# PhotonOnAStick-Wide.net
KiCad netlist of a schematic drawn in EAGLE
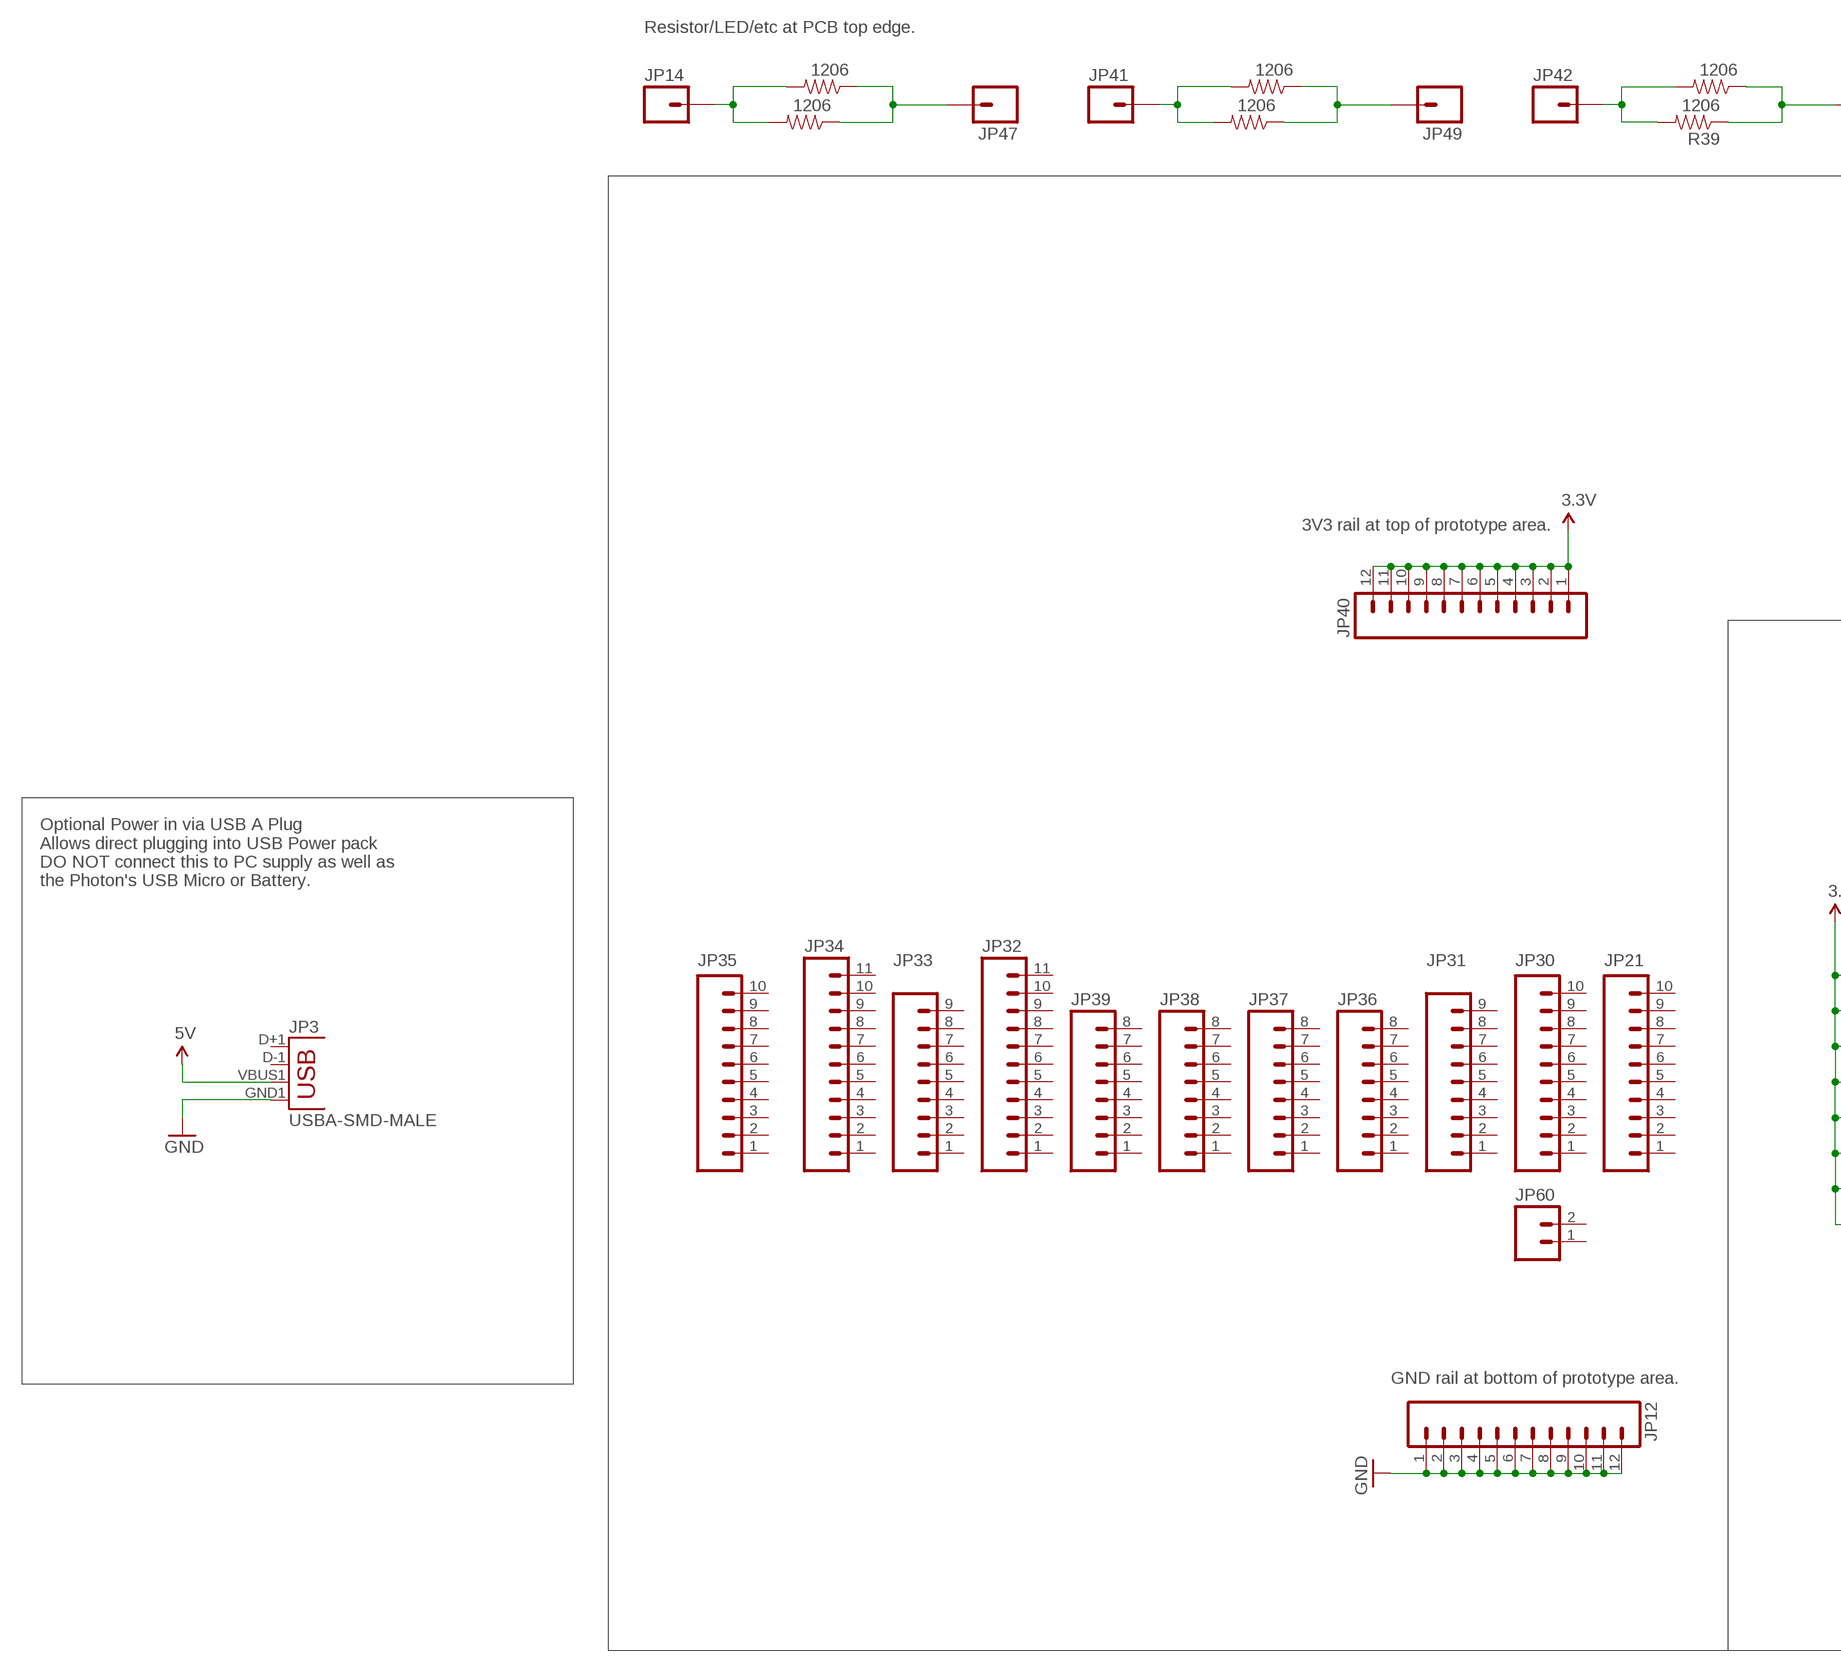
[diagram p0: schematic, sheet 1, part 1 of 2]
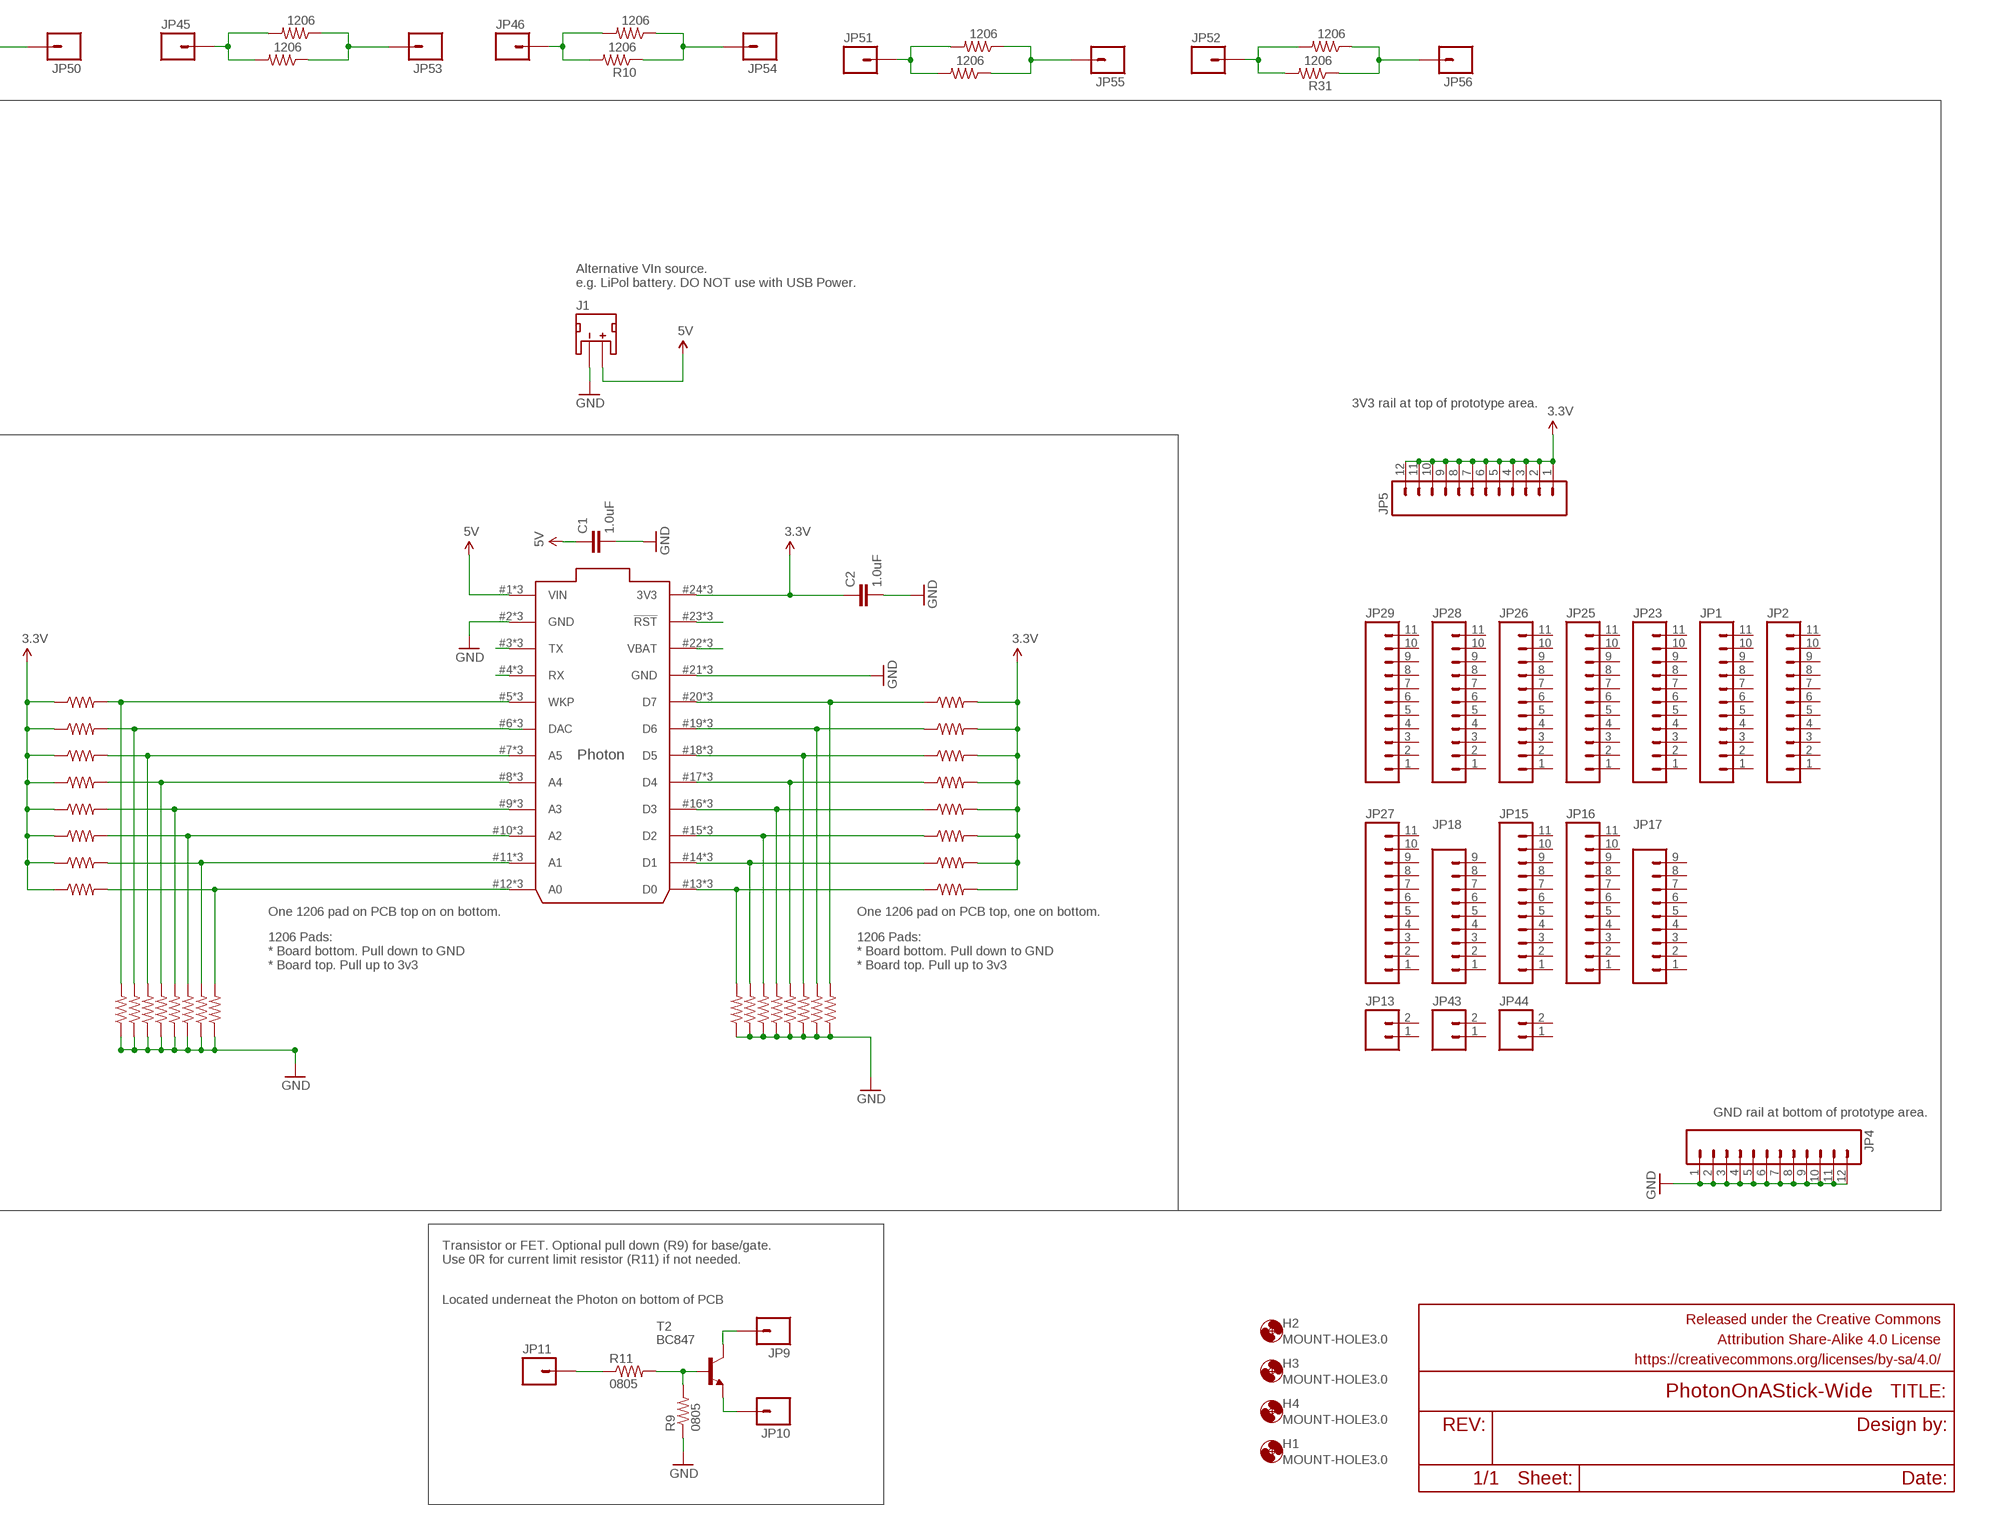
[diagram p1: schematic, sheet 1, part 2 of 2]

(export (version "E")
  (design (tool "Eeschema 10.0.6"))
  (components
    (comp (ref "C1")
      (value "1.0uF")
      (footprint "eagle-import:0805-CAP")
      (libsource (lib "eagle-import") (part "1.0UF-25V-+80/-20(0805){dblquote}"))
    )
    (comp (ref "C2")
      (value "1.0uF")
      (footprint "eagle-import:0805-CAP")
      (libsource (lib "eagle-import") (part "1.0UF-25V-+80/-20(0805){dblquote}"))
    )
    (comp (ref "FRAME1")
      (value "FRAME-LEDGER")
      (footprint "eagle-import:CREATIVE_COMMONS")
      (libsource (lib "eagle-import") (part "FRAME-LEDGER"))
    )
    (comp (ref "H1")
      (value "MOUNT-HOLE3.0")
      (footprint "eagle-import:3,0")
      (libsource (lib "eagle-import") (part "MOUNT-HOLE3.0"))
    )
    (comp (ref "H2")
      (value "MOUNT-HOLE3.0")
      (footprint "eagle-import:3,0")
      (libsource (lib "eagle-import") (part "MOUNT-HOLE3.0"))
    )
    (comp (ref "H3")
      (value "MOUNT-HOLE3.0")
      (footprint "eagle-import:3,0")
      (libsource (lib "eagle-import") (part "MOUNT-HOLE3.0"))
    )
    (comp (ref "H4")
      (value "MOUNT-HOLE3.0")
      (footprint "eagle-import:3,0")
      (libsource (lib "eagle-import") (part "MOUNT-HOLE3.0"))
    )
    (comp (ref "IC1")
      (value "PHOTON_WITH_STACKABLE_HEADERS")
      (footprint "eagle-import:PHOTON_STACKABLE")
      (libsource (lib "eagle-import") (part "PHOTON_WITH_STACKABLE_HEADERS"))
    )
    (comp (ref "J1")
      (value "JST_2MM_MALE")
      (footprint "eagle-import:JST-2-SMD")
      (libsource (lib "eagle-import") (part "JST_2MM_MALE"))
    )
    (comp (ref "JP1")
      (value "M111X11_NO_SILK")
      (footprint "eagle-import:1X11_NO_SILK")
      (libsource (lib "eagle-import") (part "M111X11_NO_SILK"))
    )
    (comp (ref "JP2")
      (value "M111X11_NO_SILK")
      (footprint "eagle-import:1X11_NO_SILK")
      (libsource (lib "eagle-import") (part "M111X11_NO_SILK"))
    )
    (comp (ref "JP3")
      (value "USBA-SMD-MALE")
      (footprint "eagle-import:USB-A-SMT-MALE")
      (libsource (lib "eagle-import") (part "USBA-SMD-MALE"))
    )
    (comp (ref "JP4")
      (value "M12PTH")
      (footprint "eagle-import:1X12")
      (libsource (lib "eagle-import") (part "M12PTH"))
    )
    (comp (ref "JP5")
      (value "M12PTH")
      (footprint "eagle-import:1X12")
      (libsource (lib "eagle-import") (part "M12PTH"))
    )
    (comp (ref "JP9")
      (value "M01PTH")
      (footprint "eagle-import:1X01")
      (libsource (lib "eagle-import") (part "M01PTH"))
    )
    (comp (ref "JP10")
      (value "M01PTH")
      (footprint "eagle-import:1X01")
      (libsource (lib "eagle-import") (part "M01PTH"))
    )
    (comp (ref "JP11")
      (value "M01PTH")
      (footprint "eagle-import:1X01")
      (libsource (lib "eagle-import") (part "M01PTH"))
    )
    (comp (ref "JP12")
      (value "M12PTH")
      (footprint "eagle-import:1X12")
      (libsource (lib "eagle-import") (part "M12PTH"))
    )
    (comp (ref "JP13")
      (value "M021X02_NO_SILK")
      (footprint "eagle-import:1X02_NO_SILK")
      (libsource (lib "eagle-import") (part "M021X02_NO_SILK"))
    )
    (comp (ref "JP14")
      (value "M01PTH")
      (footprint "eagle-import:1X01")
      (libsource (lib "eagle-import") (part "M01PTH"))
    )
    (comp (ref "JP15")
      (value "M111X11_NO_SILK")
      (footprint "eagle-import:1X11_NO_SILK")
      (libsource (lib "eagle-import") (part "M111X11_NO_SILK"))
    )
    (comp (ref "JP16")
      (value "M111X11_NO_SILK")
      (footprint "eagle-import:1X11_NO_SILK")
      (libsource (lib "eagle-import") (part "M111X11_NO_SILK"))
    )
    (comp (ref "JP17")
      (value "M09NO_SILK")
      (footprint "eagle-import:1X09_NO_SILK")
      (libsource (lib "eagle-import") (part "M09NO_SILK"))
    )
    (comp (ref "JP18")
      (value "M09NO_SILK")
      (footprint "eagle-import:1X09_NO_SILK")
      (libsource (lib "eagle-import") (part "M09NO_SILK"))
    )
    (comp (ref "JP21")
      (value "M10NO_SILK_PTH_FEMALE")
      (footprint "eagle-import:1X10_NO_SILK")
      (libsource (lib "eagle-import") (part "M10NO_SILK_PTH_FEMALE"))
    )
    (comp (ref "JP23")
      (value "M111X11_NO_SILK")
      (footprint "eagle-import:1X11_NO_SILK")
      (libsource (lib "eagle-import") (part "M111X11_NO_SILK"))
    )
    (comp (ref "JP25")
      (value "M111X11_NO_SILK")
      (footprint "eagle-import:1X11_NO_SILK")
      (libsource (lib "eagle-import") (part "M111X11_NO_SILK"))
    )
    (comp (ref "JP26")
      (value "M111X11_NO_SILK")
      (footprint "eagle-import:1X11_NO_SILK")
      (libsource (lib "eagle-import") (part "M111X11_NO_SILK"))
    )
    (comp (ref "JP27")
      (value "M111X11_NO_SILK")
      (footprint "eagle-import:1X11_NO_SILK")
      (libsource (lib "eagle-import") (part "M111X11_NO_SILK"))
    )
    (comp (ref "JP28")
      (value "M111X11_NO_SILK")
      (footprint "eagle-import:1X11_NO_SILK")
      (libsource (lib "eagle-import") (part "M111X11_NO_SILK"))
    )
    (comp (ref "JP29")
      (value "M111X11_NO_SILK")
      (footprint "eagle-import:1X11_NO_SILK")
      (libsource (lib "eagle-import") (part "M111X11_NO_SILK"))
    )
    (comp (ref "JP30")
      (value "M10NO_SILK_PTH_FEMALE")
      (footprint "eagle-import:1X10_NO_SILK")
      (libsource (lib "eagle-import") (part "M10NO_SILK_PTH_FEMALE"))
    )
    (comp (ref "JP31")
      (value "M09NO_SILK")
      (footprint "eagle-import:1X09_NO_SILK")
      (libsource (lib "eagle-import") (part "M09NO_SILK"))
    )
    (comp (ref "JP32")
      (value "M111X11_NO_SILK")
      (footprint "eagle-import:1X11_NO_SILK")
      (libsource (lib "eagle-import") (part "M111X11_NO_SILK"))
    )
    (comp (ref "JP33")
      (value "M09NO_SILK")
      (footprint "eagle-import:1X09_NO_SILK")
      (libsource (lib "eagle-import") (part "M09NO_SILK"))
    )
    (comp (ref "JP34")
      (value "M111X11_NO_SILK")
      (footprint "eagle-import:1X11_NO_SILK")
      (libsource (lib "eagle-import") (part "M111X11_NO_SILK"))
    )
    (comp (ref "JP35")
      (value "M10NO_SILK_PTH_FEMALE")
      (footprint "eagle-import:1X10_NO_SILK")
      (libsource (lib "eagle-import") (part "M10NO_SILK_PTH_FEMALE"))
    )
    (comp (ref "JP36")
      (value "M08NO_SILK_FEMALE_PTH")
      (footprint "eagle-import:1X08_NO_SILK")
      (libsource (lib "eagle-import") (part "M08NO_SILK_FEMALE_PTH"))
    )
    (comp (ref "JP37")
      (value "M08NO_SILK_FEMALE_PTH")
      (footprint "eagle-import:1X08_NO_SILK")
      (libsource (lib "eagle-import") (part "M08NO_SILK_FEMALE_PTH"))
    )
    (comp (ref "JP38")
      (value "M08NO_SILK_FEMALE_PTH")
      (footprint "eagle-import:1X08_NO_SILK")
      (libsource (lib "eagle-import") (part "M08NO_SILK_FEMALE_PTH"))
    )
    (comp (ref "JP39")
      (value "M08NO_SILK_FEMALE_PTH")
      (footprint "eagle-import:1X08_NO_SILK")
      (libsource (lib "eagle-import") (part "M08NO_SILK_FEMALE_PTH"))
    )
    (comp (ref "JP40")
      (value "M12PTH")
      (footprint "eagle-import:1X12")
      (libsource (lib "eagle-import") (part "M12PTH"))
    )
    (comp (ref "JP41")
      (value "M01PTH")
      (footprint "eagle-import:1X01")
      (libsource (lib "eagle-import") (part "M01PTH"))
    )
    (comp (ref "JP42")
      (value "M01PTH")
      (footprint "eagle-import:1X01")
      (libsource (lib "eagle-import") (part "M01PTH"))
    )
    (comp (ref "JP43")
      (value "M021X02_NO_SILK")
      (footprint "eagle-import:1X02_NO_SILK")
      (libsource (lib "eagle-import") (part "M021X02_NO_SILK"))
    )
    (comp (ref "JP44")
      (value "M021X02_NO_SILK")
      (footprint "eagle-import:1X02_NO_SILK")
      (libsource (lib "eagle-import") (part "M021X02_NO_SILK"))
    )
    (comp (ref "JP45")
      (value "M01PTH")
      (footprint "eagle-import:1X01")
      (libsource (lib "eagle-import") (part "M01PTH"))
    )
    (comp (ref "JP46")
      (value "M01PTH")
      (footprint "eagle-import:1X01")
      (libsource (lib "eagle-import") (part "M01PTH"))
    )
    (comp (ref "JP47")
      (value "M01PTH")
      (footprint "eagle-import:1X01")
      (libsource (lib "eagle-import") (part "M01PTH"))
    )
    (comp (ref "JP49")
      (value "M01PTH")
      (footprint "eagle-import:1X01")
      (libsource (lib "eagle-import") (part "M01PTH"))
    )
    (comp (ref "JP50")
      (value "M01PTH")
      (footprint "eagle-import:1X01")
      (libsource (lib "eagle-import") (part "M01PTH"))
    )
    (comp (ref "JP51")
      (value "M01PTH")
      (footprint "eagle-import:1X01")
      (libsource (lib "eagle-import") (part "M01PTH"))
    )
    (comp (ref "JP52")
      (value "M01PTH")
      (footprint "eagle-import:1X01")
      (libsource (lib "eagle-import") (part "M01PTH"))
    )
    (comp (ref "JP53")
      (value "M01PTH")
      (footprint "eagle-import:1X01")
      (libsource (lib "eagle-import") (part "M01PTH"))
    )
    (comp (ref "JP54")
      (value "M01PTH")
      (footprint "eagle-import:1X01")
      (libsource (lib "eagle-import") (part "M01PTH"))
    )
    (comp (ref "JP55")
      (value "M01PTH")
      (footprint "eagle-import:1X01")
      (libsource (lib "eagle-import") (part "M01PTH"))
    )
    (comp (ref "JP56")
      (value "M01PTH")
      (footprint "eagle-import:1X01")
      (libsource (lib "eagle-import") (part "M01PTH"))
    )
    (comp (ref "JP60")
      (value "M021X02_NO_SILK")
      (footprint "eagle-import:1X02_NO_SILK")
      (libsource (lib "eagle-import") (part "M021X02_NO_SILK"))
    )
    (comp (ref "R1")
      (value "1206")
      (footprint "eagle-import:1206")
      (libsource (lib "eagle-import") (part "RESISTOR1206"))
    )
    (comp (ref "R2")
      (value "1206")
      (footprint "eagle-import:1206")
      (libsource (lib "eagle-import") (part "RESISTOR1206"))
    )
    (comp (ref "R3")
      (value "1206")
      (footprint "eagle-import:1206")
      (libsource (lib "eagle-import") (part "RESISTOR1206"))
    )
    (comp (ref "R4")
      (value "1206")
      (footprint "eagle-import:1206")
      (libsource (lib "eagle-import") (part "RESISTOR1206"))
    )
    (comp (ref "R5")
      (value "1206")
      (footprint "eagle-import:1206")
      (libsource (lib "eagle-import") (part "RESISTOR1206"))
    )
    (comp (ref "R6")
      (value "1206")
      (footprint "eagle-import:1206")
      (libsource (lib "eagle-import") (part "RESISTOR1206"))
    )
    (comp (ref "R7")
      (value "1206")
      (footprint "eagle-import:1206")
      (libsource (lib "eagle-import") (part "RESISTOR1206"))
    )
    (comp (ref "R8")
      (value "1206")
      (footprint "eagle-import:1206")
      (libsource (lib "eagle-import") (part "RESISTOR1206"))
    )
    (comp (ref "R9")
      (value "0805")
      (footprint "eagle-import:0805")
      (libsource (lib "eagle-import") (part "RESISTOR0805-RES"))
    )
    (comp (ref "R10")
      (value "1206")
      (footprint "eagle-import:1206")
      (libsource (lib "eagle-import") (part "RESISTOR1206"))
    )
    (comp (ref "R11")
      (value "0805")
      (footprint "eagle-import:0805")
      (libsource (lib "eagle-import") (part "RESISTOR0805-RES"))
    )
    (comp (ref "R12")
      (value "1206")
      (footprint "eagle-import:1206")
      (libsource (lib "eagle-import") (part "RESISTOR1206"))
    )
    (comp (ref "R13")
      (value "1206")
      (footprint "eagle-import:1206")
      (libsource (lib "eagle-import") (part "RESISTOR1206"))
    )
    (comp (ref "R14")
      (value "1206")
      (footprint "eagle-import:1206")
      (libsource (lib "eagle-import") (part "RESISTOR1206"))
    )
    (comp (ref "R15")
      (value "1206")
      (footprint "eagle-import:1206")
      (libsource (lib "eagle-import") (part "RESISTOR1206"))
    )
    (comp (ref "R16")
      (value "1206")
      (footprint "eagle-import:1206")
      (libsource (lib "eagle-import") (part "RESISTOR1206"))
    )
    (comp (ref "R17")
      (value "1206")
      (footprint "eagle-import:1206")
      (libsource (lib "eagle-import") (part "RESISTOR1206"))
    )
    (comp (ref "R18")
      (value "1206")
      (footprint "eagle-import:1206")
      (libsource (lib "eagle-import") (part "RESISTOR1206"))
    )
    (comp (ref "R19")
      (value "1206")
      (footprint "eagle-import:1206")
      (libsource (lib "eagle-import") (part "RESISTOR1206"))
    )
    (comp (ref "R20")
      (value "1206")
      (footprint "eagle-import:1206")
      (libsource (lib "eagle-import") (part "RESISTOR1206"))
    )
    (comp (ref "R21")
      (value "1206")
      (footprint "eagle-import:1206")
      (libsource (lib "eagle-import") (part "RESISTOR1206"))
    )
    (comp (ref "R22")
      (value "1206")
      (footprint "eagle-import:1206")
      (libsource (lib "eagle-import") (part "RESISTOR1206"))
    )
    (comp (ref "R23")
      (value "1206")
      (footprint "eagle-import:1206")
      (libsource (lib "eagle-import") (part "RESISTOR1206"))
    )
    (comp (ref "R24")
      (value "1206")
      (footprint "eagle-import:1206")
      (libsource (lib "eagle-import") (part "RESISTOR1206"))
    )
    (comp (ref "R25")
      (value "1206")
      (footprint "eagle-import:1206")
      (libsource (lib "eagle-import") (part "RESISTOR1206"))
    )
    (comp (ref "R26")
      (value "1206")
      (footprint "eagle-import:1206")
      (libsource (lib "eagle-import") (part "RESISTOR1206"))
    )
    (comp (ref "R27")
      (value "1206")
      (footprint "eagle-import:1206")
      (libsource (lib "eagle-import") (part "RESISTOR1206"))
    )
    (comp (ref "R28")
      (value "1206")
      (footprint "eagle-import:1206")
      (libsource (lib "eagle-import") (part "RESISTOR1206"))
    )
    (comp (ref "R29")
      (value "1206")
      (footprint "eagle-import:1206")
      (libsource (lib "eagle-import") (part "RESISTOR1206"))
    )
    (comp (ref "R30")
      (value "1206")
      (footprint "eagle-import:1206")
      (libsource (lib "eagle-import") (part "RESISTOR1206"))
    )
    (comp (ref "R31")
      (value "1206")
      (footprint "eagle-import:1206")
      (libsource (lib "eagle-import") (part "RESISTOR1206"))
    )
    (comp (ref "R32")
      (value "1206")
      (footprint "eagle-import:1206")
      (libsource (lib "eagle-import") (part "RESISTOR1206"))
    )
    (comp (ref "R34")
      (value "1206")
      (footprint "eagle-import:1206")
      (libsource (lib "eagle-import") (part "RESISTOR1206"))
    )
    (comp (ref "R35")
      (value "1206")
      (footprint "eagle-import:1206")
      (libsource (lib "eagle-import") (part "RESISTOR1206"))
    )
    (comp (ref "R36")
      (value "1206")
      (footprint "eagle-import:1206")
      (libsource (lib "eagle-import") (part "RESISTOR1206"))
    )
    (comp (ref "R37")
      (value "1206")
      (footprint "eagle-import:1206")
      (libsource (lib "eagle-import") (part "RESISTOR1206"))
    )
    (comp (ref "R39")
      (value "1206")
      (footprint "eagle-import:1206")
      (libsource (lib "eagle-import") (part "RESISTOR1206"))
    )
    (comp (ref "R40")
      (value "1206")
      (footprint "eagle-import:1206")
      (libsource (lib "eagle-import") (part "RESISTOR1206"))
    )
    (comp (ref "R41")
      (value "1206")
      (footprint "eagle-import:1206")
      (libsource (lib "eagle-import") (part "RESISTOR1206"))
    )
    (comp (ref "R42")
      (value "1206")
      (footprint "eagle-import:1206")
      (libsource (lib "eagle-import") (part "RESISTOR1206"))
    )
    (comp (ref "R43")
      (value "1206")
      (footprint "eagle-import:1206")
      (libsource (lib "eagle-import") (part "RESISTOR1206"))
    )
    (comp (ref "R44")
      (value "1206")
      (footprint "eagle-import:1206")
      (libsource (lib "eagle-import") (part "RESISTOR1206"))
    )
    (comp (ref "R45")
      (value "1206")
      (footprint "eagle-import:1206")
      (libsource (lib "eagle-import") (part "RESISTOR1206"))
    )
    (comp (ref "R46")
      (value "1206")
      (footprint "eagle-import:1206")
      (libsource (lib "eagle-import") (part "RESISTOR1206"))
    )
    (comp (ref "R47")
      (value "1206")
      (footprint "eagle-import:1206")
      (libsource (lib "eagle-import") (part "RESISTOR1206"))
    )
    (comp (ref "R48")
      (value "1206")
      (footprint "eagle-import:1206")
      (libsource (lib "eagle-import") (part "RESISTOR1206"))
    )
    (comp (ref "R49")
      (value "1206")
      (footprint "eagle-import:1206")
      (libsource (lib "eagle-import") (part "RESISTOR1206"))
    )
    (comp (ref "R50")
      (value "1206")
      (footprint "eagle-import:1206")
      (libsource (lib "eagle-import") (part "RESISTOR1206"))
    )
    (comp (ref "T2")
      (value "BC847")
      (footprint "eagle-import:SOT23")
      (libsource (lib "eagle-import") (part "BC847"))
    )
  )
  (nets
    (net (code "1") (name "3.3V") (class "Default")
      (node (ref "C2") (pin "1") (pinfunction "1_1") (pintype "passive"))
      (node (ref "IC1") (pin "#24") (pinfunction "3V3_#24") (pintype "power_in"))
      (node (ref "IC1") (pin "24") (pinfunction "3V3_24") (pintype "power_in"))
      (node (ref "IC1") (pin "@24") (pinfunction "3V3_@24") (pintype "power_in"))
      (node (ref "JP40") (pin "1") (pinfunction "1_1") (pintype "passive"))
      (node (ref "JP40") (pin "10") (pinfunction "10_10") (pintype "passive"))
      (node (ref "JP40") (pin "11") (pinfunction "11_11") (pintype "passive"))
      (node (ref "JP40") (pin "12") (pinfunction "12_12") (pintype "passive"))
      (node (ref "JP40") (pin "2") (pinfunction "2_2") (pintype "passive"))
      (node (ref "JP40") (pin "3") (pinfunction "3_3") (pintype "passive"))
      (node (ref "JP40") (pin "4") (pinfunction "4_4") (pintype "passive"))
      (node (ref "JP40") (pin "5") (pinfunction "5_5") (pintype "passive"))
      (node (ref "JP40") (pin "6") (pinfunction "6_6") (pintype "passive"))
      (node (ref "JP40") (pin "7") (pinfunction "7_7") (pintype "passive"))
      (node (ref "JP40") (pin "8") (pinfunction "8_8") (pintype "passive"))
      (node (ref "JP40") (pin "9") (pinfunction "9_9") (pintype "passive"))
      (node (ref "JP5") (pin "1") (pinfunction "1_1") (pintype "passive"))
      (node (ref "JP5") (pin "10") (pinfunction "10_10") (pintype "passive"))
      (node (ref "JP5") (pin "11") (pinfunction "11_11") (pintype "passive"))
      (node (ref "JP5") (pin "12") (pinfunction "12_12") (pintype "passive"))
      (node (ref "JP5") (pin "2") (pinfunction "2_2") (pintype "passive"))
      (node (ref "JP5") (pin "3") (pinfunction "3_3") (pintype "passive"))
      (node (ref "JP5") (pin "4") (pinfunction "4_4") (pintype "passive"))
      (node (ref "JP5") (pin "5") (pinfunction "5_5") (pintype "passive"))
      (node (ref "JP5") (pin "6") (pinfunction "6_6") (pintype "passive"))
      (node (ref "JP5") (pin "7") (pinfunction "7_7") (pintype "passive"))
      (node (ref "JP5") (pin "8") (pinfunction "8_8") (pintype "passive"))
      (node (ref "JP5") (pin "9") (pinfunction "9_9") (pintype "passive"))
      (node (ref "R1") (pin "1") (pinfunction "1_1") (pintype "passive"))
      (node (ref "R12") (pin "1") (pinfunction "1_1") (pintype "passive"))
      (node (ref "R15") (pin "1") (pinfunction "1_1") (pintype "passive"))
      (node (ref "R18") (pin "2") (pinfunction "2_2") (pintype "passive"))
      (node (ref "R2") (pin "1") (pinfunction "1_1") (pintype "passive"))
      (node (ref "R23") (pin "2") (pinfunction "2_2") (pintype "passive"))
      (node (ref "R25") (pin "2") (pinfunction "2_2") (pintype "passive"))
      (node (ref "R26") (pin "2") (pinfunction "2_2") (pintype "passive"))
      (node (ref "R27") (pin "2") (pinfunction "2_2") (pintype "passive"))
      (node (ref "R28") (pin "2") (pinfunction "2_2") (pintype "passive"))
      (node (ref "R29") (pin "2") (pinfunction "2_2") (pintype "passive"))
      (node (ref "R3") (pin "1") (pinfunction "1_1") (pintype "passive"))
      (node (ref "R4") (pin "1") (pinfunction "1_1") (pintype "passive"))
      (node (ref "R5") (pin "2") (pinfunction "2_2") (pintype "passive"))
      (node (ref "R6") (pin "1") (pinfunction "1_1") (pintype "passive"))
      (node (ref "R7") (pin "1") (pinfunction "1_1") (pintype "passive"))
    )
    (net (code "2") (name "5V") (class "Default")
      (node (ref "C1") (pin "1") (pinfunction "1_1") (pintype "passive"))
      (node (ref "IC1") (pin "#1") (pinfunction "VIN_#1") (pintype "power_in"))
      (node (ref "IC1") (pin "1") (pinfunction "VIN_1") (pintype "power_in"))
      (node (ref "IC1") (pin "@1") (pinfunction "VIN_@1") (pintype "power_in"))
      (node (ref "J1") (pin "2") (pinfunction "+_2") (pintype "bidirectional"))
      (node (ref "JP3") (pin "VBUS1") (pinfunction "VBUS_VBUS1") (pintype "bidirectional"))
    )
    (net (code "3") (name "GND") (class "Default")
      (node (ref "C1") (pin "2") (pinfunction "2_2") (pintype "passive"))
      (node (ref "C2") (pin "2") (pinfunction "2_2") (pintype "passive"))
      (node (ref "IC1") (pin "#2") (pinfunction "GND_#2") (pintype "power_in"))
      (node (ref "IC1") (pin "#21") (pinfunction "GND_#21") (pintype "power_in"))
      (node (ref "IC1") (pin "2") (pinfunction "GND_2") (pintype "power_in"))
      (node (ref "IC1") (pin "21") (pinfunction "GND_21") (pintype "power_in"))
      (node (ref "IC1") (pin "@2") (pinfunction "GND_@2") (pintype "power_in"))
      (node (ref "IC1") (pin "@21") (pinfunction "GND_@21") (pintype "power_in"))
      (node (ref "J1") (pin "1") (pinfunction "-_1") (pintype "bidirectional"))
      (node (ref "JP12") (pin "1") (pinfunction "1_1") (pintype "passive"))
      (node (ref "JP12") (pin "10") (pinfunction "10_10") (pintype "passive"))
      (node (ref "JP12") (pin "11") (pinfunction "11_11") (pintype "passive"))
      (node (ref "JP12") (pin "12") (pinfunction "12_12") (pintype "passive"))
      (node (ref "JP12") (pin "2") (pinfunction "2_2") (pintype "passive"))
      (node (ref "JP12") (pin "3") (pinfunction "3_3") (pintype "passive"))
      (node (ref "JP12") (pin "4") (pinfunction "4_4") (pintype "passive"))
      (node (ref "JP12") (pin "5") (pinfunction "5_5") (pintype "passive"))
      (node (ref "JP12") (pin "6") (pinfunction "6_6") (pintype "passive"))
      (node (ref "JP12") (pin "7") (pinfunction "7_7") (pintype "passive"))
      (node (ref "JP12") (pin "8") (pinfunction "8_8") (pintype "passive"))
      (node (ref "JP12") (pin "9") (pinfunction "9_9") (pintype "passive"))
      (node (ref "JP3") (pin "GND1") (pinfunction "GND_GND1") (pintype "bidirectional"))
      (node (ref "JP4") (pin "1") (pinfunction "1_1") (pintype "passive"))
      (node (ref "JP4") (pin "10") (pinfunction "10_10") (pintype "passive"))
      (node (ref "JP4") (pin "11") (pinfunction "11_11") (pintype "passive"))
      (node (ref "JP4") (pin "12") (pinfunction "12_12") (pintype "passive"))
      (node (ref "JP4") (pin "2") (pinfunction "2_2") (pintype "passive"))
      (node (ref "JP4") (pin "3") (pinfunction "3_3") (pintype "passive"))
      (node (ref "JP4") (pin "4") (pinfunction "4_4") (pintype "passive"))
      (node (ref "JP4") (pin "5") (pinfunction "5_5") (pintype "passive"))
      (node (ref "JP4") (pin "6") (pinfunction "6_6") (pintype "passive"))
      (node (ref "JP4") (pin "7") (pinfunction "7_7") (pintype "passive"))
      (node (ref "JP4") (pin "8") (pinfunction "8_8") (pintype "passive"))
      (node (ref "JP4") (pin "9") (pinfunction "9_9") (pintype "passive"))
      (node (ref "R13") (pin "1") (pinfunction "1_1") (pintype "passive"))
      (node (ref "R14") (pin "1") (pinfunction "1_1") (pintype "passive"))
      (node (ref "R16") (pin "1") (pinfunction "1_1") (pintype "passive"))
      (node (ref "R19") (pin "1") (pinfunction "1_1") (pintype "passive"))
      (node (ref "R20") (pin "1") (pinfunction "1_1") (pintype "passive"))
      (node (ref "R21") (pin "1") (pinfunction "1_1") (pintype "passive"))
      (node (ref "R22") (pin "1") (pinfunction "1_1") (pintype "passive"))
      (node (ref "R42") (pin "1") (pinfunction "1_1") (pintype "passive"))
      (node (ref "R43") (pin "1") (pinfunction "1_1") (pintype "passive"))
      (node (ref "R45") (pin "1") (pinfunction "1_1") (pintype "passive"))
      (node (ref "R46") (pin "1") (pinfunction "1_1") (pintype "passive"))
      (node (ref "R47") (pin "1") (pinfunction "1_1") (pintype "passive"))
      (node (ref "R48") (pin "1") (pinfunction "1_1") (pintype "passive"))
      (node (ref "R49") (pin "1") (pinfunction "1_1") (pintype "passive"))
      (node (ref "R50") (pin "1") (pinfunction "1_1") (pintype "passive"))
      (node (ref "R8") (pin "1") (pinfunction "1_1") (pintype "passive"))
      (node (ref "R9") (pin "1") (pinfunction "1_1") (pintype "passive"))
    )
    (net (code "4") (name "Net-(IC1-A0-Pad#12)") (class "Default")
      (node (ref "IC1") (pin "#12") (pinfunction "A0_#12") (pintype "bidirectional"))
      (node (ref "IC1") (pin "12") (pinfunction "A0_12") (pintype "bidirectional"))
      (node (ref "IC1") (pin "@12") (pinfunction "A0_@12") (pintype "bidirectional"))
      (node (ref "R22") (pin "2") (pinfunction "2_2") (pintype "passive"))
      (node (ref "R7") (pin "2") (pinfunction "2_2") (pintype "passive"))
    )
    (net (code "5") (name "Net-(IC1-A1-Pad#11)") (class "Default")
      (node (ref "IC1") (pin "#11") (pinfunction "A1_#11") (pintype "bidirectional"))
      (node (ref "IC1") (pin "11") (pinfunction "A1_11") (pintype "bidirectional"))
      (node (ref "IC1") (pin "@11") (pinfunction "A1_@11") (pintype "bidirectional"))
      (node (ref "R21") (pin "2") (pinfunction "2_2") (pintype "passive"))
      (node (ref "R6") (pin "2") (pinfunction "2_2") (pintype "passive"))
    )
    (net (code "6") (name "Net-(IC1-A2-Pad#10)") (class "Default")
      (node (ref "IC1") (pin "#10") (pinfunction "A2_#10") (pintype "bidirectional"))
      (node (ref "IC1") (pin "10") (pinfunction "A2_10") (pintype "bidirectional"))
      (node (ref "IC1") (pin "@10") (pinfunction "A2_@10") (pintype "bidirectional"))
      (node (ref "R20") (pin "2") (pinfunction "2_2") (pintype "passive"))
      (node (ref "R4") (pin "2") (pinfunction "2_2") (pintype "passive"))
    )
    (net (code "7") (name "Net-(IC1-A3-Pad#9)") (class "Default")
      (node (ref "IC1") (pin "#9") (pinfunction "A3_#9") (pintype "bidirectional"))
      (node (ref "IC1") (pin "9") (pinfunction "A3_9") (pintype "bidirectional"))
      (node (ref "IC1") (pin "@9") (pinfunction "A3_@9") (pintype "bidirectional"))
      (node (ref "R19") (pin "2") (pinfunction "2_2") (pintype "passive"))
      (node (ref "R3") (pin "2") (pinfunction "2_2") (pintype "passive"))
    )
    (net (code "8") (name "Net-(IC1-A4-Pad#8)") (class "Default")
      (node (ref "IC1") (pin "#8") (pinfunction "A4_#8") (pintype "bidirectional"))
      (node (ref "IC1") (pin "8") (pinfunction "A4_8") (pintype "bidirectional"))
      (node (ref "IC1") (pin "@8") (pinfunction "A4_@8") (pintype "bidirectional"))
      (node (ref "R14") (pin "2") (pinfunction "2_2") (pintype "passive"))
      (node (ref "R2") (pin "2") (pinfunction "2_2") (pintype "passive"))
    )
    (net (code "9") (name "Net-(IC1-A5-Pad#7)") (class "Default")
      (node (ref "IC1") (pin "#7") (pinfunction "A5_#7") (pintype "bidirectional"))
      (node (ref "IC1") (pin "7") (pinfunction "A5_7") (pintype "bidirectional"))
      (node (ref "IC1") (pin "@7") (pinfunction "A5_@7") (pintype "bidirectional"))
      (node (ref "R1") (pin "2") (pinfunction "2_2") (pintype "passive"))
      (node (ref "R13") (pin "2") (pinfunction "2_2") (pintype "passive"))
    )
    (net (code "10") (name "Net-(IC1-D0-Pad#13)") (class "Default")
      (node (ref "IC1") (pin "#13") (pinfunction "D0_#13") (pintype "bidirectional"))
      (node (ref "IC1") (pin "13") (pinfunction "D0_13") (pintype "bidirectional"))
      (node (ref "IC1") (pin "@13") (pinfunction "D0_@13") (pintype "bidirectional"))
      (node (ref "R26") (pin "1") (pinfunction "1_1") (pintype "passive"))
      (node (ref "R42") (pin "2") (pinfunction "2_2") (pintype "passive"))
    )
    (net (code "11") (name "Net-(IC1-D1-Pad#14)") (class "Default")
      (node (ref "IC1") (pin "#14") (pinfunction "D1_#14") (pintype "bidirectional"))
      (node (ref "IC1") (pin "14") (pinfunction "D1_14") (pintype "bidirectional"))
      (node (ref "IC1") (pin "@14") (pinfunction "D1_@14") (pintype "bidirectional"))
      (node (ref "R25") (pin "1") (pinfunction "1_1") (pintype "passive"))
      (node (ref "R43") (pin "2") (pinfunction "2_2") (pintype "passive"))
    )
    (net (code "12") (name "Net-(IC1-D2-Pad#15)") (class "Default")
      (node (ref "IC1") (pin "#15") (pinfunction "D2_#15") (pintype "bidirectional"))
      (node (ref "IC1") (pin "15") (pinfunction "D2_15") (pintype "bidirectional"))
      (node (ref "IC1") (pin "@15") (pinfunction "D2_@15") (pintype "bidirectional"))
      (node (ref "R27") (pin "1") (pinfunction "1_1") (pintype "passive"))
      (node (ref "R45") (pin "2") (pinfunction "2_2") (pintype "passive"))
    )
    (net (code "13") (name "Net-(IC1-D3-Pad#16)") (class "Default")
      (node (ref "IC1") (pin "#16") (pinfunction "D3_#16") (pintype "bidirectional"))
      (node (ref "IC1") (pin "16") (pinfunction "D3_16") (pintype "bidirectional"))
      (node (ref "IC1") (pin "@16") (pinfunction "D3_@16") (pintype "bidirectional"))
      (node (ref "R28") (pin "1") (pinfunction "1_1") (pintype "passive"))
      (node (ref "R46") (pin "2") (pinfunction "2_2") (pintype "passive"))
    )
    (net (code "14") (name "Net-(IC1-D4-Pad#17)") (class "Default")
      (node (ref "IC1") (pin "#17") (pinfunction "D4_#17") (pintype "bidirectional"))
      (node (ref "IC1") (pin "17") (pinfunction "D4_17") (pintype "bidirectional"))
      (node (ref "IC1") (pin "@17") (pinfunction "D4_@17") (pintype "bidirectional"))
      (node (ref "R29") (pin "1") (pinfunction "1_1") (pintype "passive"))
      (node (ref "R47") (pin "2") (pinfunction "2_2") (pintype "passive"))
    )
    (net (code "15") (name "Net-(IC1-D5-Pad#18)") (class "Default")
      (node (ref "IC1") (pin "#18") (pinfunction "D5_#18") (pintype "bidirectional"))
      (node (ref "IC1") (pin "18") (pinfunction "D5_18") (pintype "bidirectional"))
      (node (ref "IC1") (pin "@18") (pinfunction "D5_@18") (pintype "bidirectional"))
      (node (ref "R23") (pin "1") (pinfunction "1_1") (pintype "passive"))
      (node (ref "R48") (pin "2") (pinfunction "2_2") (pintype "passive"))
    )
    (net (code "16") (name "Net-(IC1-D6-Pad#19)") (class "Default")
      (node (ref "IC1") (pin "#19") (pinfunction "D6_#19") (pintype "bidirectional"))
      (node (ref "IC1") (pin "19") (pinfunction "D6_19") (pintype "bidirectional"))
      (node (ref "IC1") (pin "@19") (pinfunction "D6_@19") (pintype "bidirectional"))
      (node (ref "R18") (pin "1") (pinfunction "1_1") (pintype "passive"))
      (node (ref "R49") (pin "2") (pinfunction "2_2") (pintype "passive"))
    )
    (net (code "17") (name "Net-(IC1-D7-Pad#20)") (class "Default")
      (node (ref "IC1") (pin "#20") (pinfunction "D7_#20") (pintype "bidirectional"))
      (node (ref "IC1") (pin "20") (pinfunction "D7_20") (pintype "bidirectional"))
      (node (ref "IC1") (pin "@20") (pinfunction "D7_@20") (pintype "bidirectional"))
      (node (ref "R5") (pin "1") (pinfunction "1_1") (pintype "passive"))
      (node (ref "R50") (pin "2") (pinfunction "2_2") (pintype "passive"))
    )
    (net (code "18") (name "Net-(IC1-DAC-Pad#6)") (class "Default")
      (node (ref "IC1") (pin "#6") (pinfunction "DAC_#6") (pintype "bidirectional"))
      (node (ref "IC1") (pin "6") (pinfunction "DAC_6") (pintype "bidirectional"))
      (node (ref "IC1") (pin "@6") (pinfunction "DAC_@6") (pintype "bidirectional"))
      (node (ref "R15") (pin "2") (pinfunction "2_2") (pintype "passive"))
      (node (ref "R16") (pin "2") (pinfunction "2_2") (pintype "passive"))
    )
    (net (code "19") (name "Net-(IC1-RX-Pad#4)") (class "Default")
      (node (ref "IC1") (pin "#4") (pinfunction "RX_#4") (pintype "bidirectional"))
      (node (ref "IC1") (pin "4") (pinfunction "RX_4") (pintype "bidirectional"))
      (node (ref "IC1") (pin "@4") (pinfunction "RX_@4") (pintype "bidirectional"))
    )
    (net (code "20") (name "Net-(IC1-TX-Pad#3)") (class "Default")
      (node (ref "IC1") (pin "#3") (pinfunction "TX_#3") (pintype "bidirectional"))
      (node (ref "IC1") (pin "3") (pinfunction "TX_3") (pintype "bidirectional"))
      (node (ref "IC1") (pin "@3") (pinfunction "TX_@3") (pintype "bidirectional"))
    )
    (net (code "21") (name "Net-(IC1-VBAT-Pad#22)") (class "Default")
      (node (ref "IC1") (pin "#22") (pinfunction "VBAT_#22") (pintype "power_in"))
      (node (ref "IC1") (pin "22") (pinfunction "VBAT_22") (pintype "power_in"))
      (node (ref "IC1") (pin "@22") (pinfunction "VBAT_@22") (pintype "power_in"))
    )
    (net (code "22") (name "Net-(IC1-WKP-Pad#5)") (class "Default")
      (node (ref "IC1") (pin "#5") (pinfunction "WKP_#5") (pintype "bidirectional"))
      (node (ref "IC1") (pin "5") (pinfunction "WKP_5") (pintype "bidirectional"))
      (node (ref "IC1") (pin "@5") (pinfunction "WKP_@5") (pintype "bidirectional"))
      (node (ref "R12") (pin "2") (pinfunction "2_2") (pintype "passive"))
      (node (ref "R8") (pin "2") (pinfunction "2_2") (pintype "passive"))
    )
    (net (code "23") (name "Net-(IC1-~{RST}-Pad#23)") (class "Default")
      (node (ref "IC1") (pin "#23") (pinfunction "~{RST}_#23") (pintype "bidirectional"))
      (node (ref "IC1") (pin "23") (pinfunction "~{RST}_23") (pintype "bidirectional"))
      (node (ref "IC1") (pin "@23") (pinfunction "~{RST}_@23") (pintype "bidirectional"))
    )
    (net (code "24") (name "Net-(JP11-Pad1)") (class "Default")
      (node (ref "JP11") (pin "1") (pinfunction "1_1") (pintype "passive"))
      (node (ref "R11") (pin "1") (pinfunction "1_1") (pintype "passive"))
    )
    (net (code "25") (name "Net-(JP14-Pad1)") (class "Default")
      (node (ref "JP14") (pin "1") (pinfunction "1_1") (pintype "passive"))
      (node (ref "R34") (pin "2") (pinfunction "2_2") (pintype "passive"))
      (node (ref "R35") (pin "2") (pinfunction "2_2") (pintype "passive"))
    )
    (net (code "26") (name "Net-(JP41-Pad1)") (class "Default")
      (node (ref "JP41") (pin "1") (pinfunction "1_1") (pintype "passive"))
      (node (ref "R40") (pin "2") (pinfunction "2_2") (pintype "passive"))
      (node (ref "R41") (pin "2") (pinfunction "2_2") (pintype "passive"))
    )
    (net (code "27") (name "Net-(JP42-Pad1)") (class "Default")
      (node (ref "JP42") (pin "1") (pinfunction "1_1") (pintype "passive"))
      (node (ref "R39") (pin "2") (pinfunction "2_2") (pintype "passive"))
      (node (ref "R44") (pin "2") (pinfunction "2_2") (pintype "passive"))
    )
    (net (code "28") (name "Net-(JP45-Pad1)") (class "Default")
      (node (ref "JP45") (pin "1") (pinfunction "1_1") (pintype "passive"))
      (node (ref "R17") (pin "2") (pinfunction "2_2") (pintype "passive"))
      (node (ref "R24") (pin "2") (pinfunction "2_2") (pintype "passive"))
    )
    (net (code "29") (name "Net-(JP46-Pad1)") (class "Default")
      (node (ref "JP46") (pin "1") (pinfunction "1_1") (pintype "passive"))
      (node (ref "R10") (pin "2") (pinfunction "2_2") (pintype "passive"))
      (node (ref "R30") (pin "2") (pinfunction "2_2") (pintype "passive"))
    )
    (net (code "30") (name "Net-(JP47-Pad1)") (class "Default")
      (node (ref "JP47") (pin "1") (pinfunction "1_1") (pintype "passive"))
      (node (ref "R34") (pin "1") (pinfunction "1_1") (pintype "passive"))
      (node (ref "R35") (pin "1") (pinfunction "1_1") (pintype "passive"))
    )
    (net (code "31") (name "Net-(JP49-Pad1)") (class "Default")
      (node (ref "JP49") (pin "1") (pinfunction "1_1") (pintype "passive"))
      (node (ref "R40") (pin "1") (pinfunction "1_1") (pintype "passive"))
      (node (ref "R41") (pin "1") (pinfunction "1_1") (pintype "passive"))
    )
    (net (code "32") (name "Net-(JP50-Pad1)") (class "Default")
      (node (ref "JP50") (pin "1") (pinfunction "1_1") (pintype "passive"))
      (node (ref "R39") (pin "1") (pinfunction "1_1") (pintype "passive"))
      (node (ref "R44") (pin "1") (pinfunction "1_1") (pintype "passive"))
    )
    (net (code "33") (name "Net-(JP51-Pad1)") (class "Default")
      (node (ref "JP51") (pin "1") (pinfunction "1_1") (pintype "passive"))
      (node (ref "R32") (pin "2") (pinfunction "2_2") (pintype "passive"))
      (node (ref "R36") (pin "2") (pinfunction "2_2") (pintype "passive"))
    )
    (net (code "34") (name "Net-(JP52-Pad1)") (class "Default")
      (node (ref "JP52") (pin "1") (pinfunction "1_1") (pintype "passive"))
      (node (ref "R31") (pin "2") (pinfunction "2_2") (pintype "passive"))
      (node (ref "R37") (pin "2") (pinfunction "2_2") (pintype "passive"))
    )
    (net (code "35") (name "Net-(JP53-Pad1)") (class "Default")
      (node (ref "JP53") (pin "1") (pinfunction "1_1") (pintype "passive"))
      (node (ref "R17") (pin "1") (pinfunction "1_1") (pintype "passive"))
      (node (ref "R24") (pin "1") (pinfunction "1_1") (pintype "passive"))
    )
    (net (code "36") (name "Net-(JP54-Pad1)") (class "Default")
      (node (ref "JP54") (pin "1") (pinfunction "1_1") (pintype "passive"))
      (node (ref "R10") (pin "1") (pinfunction "1_1") (pintype "passive"))
      (node (ref "R30") (pin "1") (pinfunction "1_1") (pintype "passive"))
    )
    (net (code "37") (name "Net-(JP55-Pad1)") (class "Default")
      (node (ref "JP55") (pin "1") (pinfunction "1_1") (pintype "passive"))
      (node (ref "R32") (pin "1") (pinfunction "1_1") (pintype "passive"))
      (node (ref "R36") (pin "1") (pinfunction "1_1") (pintype "passive"))
    )
    (net (code "38") (name "Net-(JP56-Pad1)") (class "Default")
      (node (ref "JP56") (pin "1") (pinfunction "1_1") (pintype "passive"))
      (node (ref "R31") (pin "1") (pinfunction "1_1") (pintype "passive"))
      (node (ref "R37") (pin "1") (pinfunction "1_1") (pintype "passive"))
    )
    (net (code "39") (name "Net-(T2-B)") (class "Default")
      (node (ref "R11") (pin "2") (pinfunction "2_2") (pintype "passive"))
      (node (ref "R9") (pin "2") (pinfunction "2_2") (pintype "passive"))
      (node (ref "T2") (pin "1") (pinfunction "B_1") (pintype "passive"))
    )
    (net (code "40") (name "Net-(T2-C)") (class "Default")
      (node (ref "JP9") (pin "1") (pinfunction "1_1") (pintype "passive"))
      (node (ref "T2") (pin "3") (pinfunction "C_3") (pintype "passive"))
    )
    (net (code "41") (name "Net-(T2-E)") (class "Default")
      (node (ref "JP10") (pin "1") (pinfunction "1_1") (pintype "passive"))
      (node (ref "T2") (pin "2") (pinfunction "E_2") (pintype "passive"))
    )
    (net (code "42") (name "unconnected-(J1-PAD1-PadNC1)") (class "Default")
      (node (ref "J1") (pin "NC1") (pinfunction "PAD1_NC1") (pintype "bidirectional"))
    )
    (net (code "43") (name "unconnected-(J1-PAD2-PadNC2)") (class "Default")
      (node (ref "J1") (pin "NC2") (pinfunction "PAD2_NC2") (pintype "bidirectional"))
    )
    (net (code "44") (name "unconnected-(JP1-Pad1)") (class "Default")
      (node (ref "JP1") (pin "1") (pinfunction "1_1") (pintype "passive"))
    )
    (net (code "45") (name "unconnected-(JP1-Pad2)") (class "Default")
      (node (ref "JP1") (pin "2") (pinfunction "2_2") (pintype "passive"))
    )
    (net (code "46") (name "unconnected-(JP1-Pad3)") (class "Default")
      (node (ref "JP1") (pin "3") (pinfunction "3_3") (pintype "passive"))
    )
    (net (code "47") (name "unconnected-(JP1-Pad4)") (class "Default")
      (node (ref "JP1") (pin "4") (pinfunction "4_4") (pintype "passive"))
    )
    (net (code "48") (name "unconnected-(JP1-Pad5)") (class "Default")
      (node (ref "JP1") (pin "5") (pinfunction "5_5") (pintype "passive"))
    )
    (net (code "49") (name "unconnected-(JP1-Pad6)") (class "Default")
      (node (ref "JP1") (pin "6") (pinfunction "6_6") (pintype "passive"))
    )
    (net (code "50") (name "unconnected-(JP1-Pad7)") (class "Default")
      (node (ref "JP1") (pin "7") (pinfunction "7_7") (pintype "passive"))
    )
    (net (code "51") (name "unconnected-(JP1-Pad8)") (class "Default")
      (node (ref "JP1") (pin "8") (pinfunction "8_8") (pintype "passive"))
    )
    (net (code "52") (name "unconnected-(JP1-Pad9)") (class "Default")
      (node (ref "JP1") (pin "9") (pinfunction "9_9") (pintype "passive"))
    )
    (net (code "53") (name "unconnected-(JP1-Pad10)") (class "Default")
      (node (ref "JP1") (pin "10") (pinfunction "10_10") (pintype "passive"))
    )
    (net (code "54") (name "unconnected-(JP1-Pad11)") (class "Default")
      (node (ref "JP1") (pin "11") (pinfunction "11_11") (pintype "passive"))
    )
    (net (code "55") (name "unconnected-(JP2-Pad1)") (class "Default")
      (node (ref "JP2") (pin "1") (pinfunction "1_1") (pintype "passive"))
    )
    (net (code "56") (name "unconnected-(JP2-Pad2)") (class "Default")
      (node (ref "JP2") (pin "2") (pinfunction "2_2") (pintype "passive"))
    )
    (net (code "57") (name "unconnected-(JP2-Pad3)") (class "Default")
      (node (ref "JP2") (pin "3") (pinfunction "3_3") (pintype "passive"))
    )
    (net (code "58") (name "unconnected-(JP2-Pad4)") (class "Default")
      (node (ref "JP2") (pin "4") (pinfunction "4_4") (pintype "passive"))
    )
    (net (code "59") (name "unconnected-(JP2-Pad5)") (class "Default")
      (node (ref "JP2") (pin "5") (pinfunction "5_5") (pintype "passive"))
    )
    (net (code "60") (name "unconnected-(JP2-Pad6)") (class "Default")
      (node (ref "JP2") (pin "6") (pinfunction "6_6") (pintype "passive"))
    )
    (net (code "61") (name "unconnected-(JP2-Pad7)") (class "Default")
      (node (ref "JP2") (pin "7") (pinfunction "7_7") (pintype "passive"))
    )
    (net (code "62") (name "unconnected-(JP2-Pad8)") (class "Default")
      (node (ref "JP2") (pin "8") (pinfunction "8_8") (pintype "passive"))
    )
    (net (code "63") (name "unconnected-(JP2-Pad9)") (class "Default")
      (node (ref "JP2") (pin "9") (pinfunction "9_9") (pintype "passive"))
    )
    (net (code "64") (name "unconnected-(JP2-Pad10)") (class "Default")
      (node (ref "JP2") (pin "10") (pinfunction "10_10") (pintype "passive"))
    )
    (net (code "65") (name "unconnected-(JP2-Pad11)") (class "Default")
      (node (ref "JP2") (pin "11") (pinfunction "11_11") (pintype "passive"))
    )
    (net (code "66") (name "unconnected-(JP3-D+-PadD+1)") (class "Default")
      (node (ref "JP3") (pin "D+1") (pinfunction "D+_D+1") (pintype "bidirectional"))
    )
    (net (code "67") (name "unconnected-(JP3-D--PadD-1)") (class "Default")
      (node (ref "JP3") (pin "D-1") (pinfunction "D-_D-1") (pintype "bidirectional"))
    )
    (net (code "68") (name "unconnected-(JP13-Pad1)") (class "Default")
      (node (ref "JP13") (pin "1") (pinfunction "1_1") (pintype "passive"))
    )
    (net (code "69") (name "unconnected-(JP13-Pad2)") (class "Default")
      (node (ref "JP13") (pin "2") (pinfunction "2_2") (pintype "passive"))
    )
    (net (code "70") (name "unconnected-(JP15-Pad1)") (class "Default")
      (node (ref "JP15") (pin "1") (pinfunction "1_1") (pintype "passive"))
    )
    (net (code "71") (name "unconnected-(JP15-Pad2)") (class "Default")
      (node (ref "JP15") (pin "2") (pinfunction "2_2") (pintype "passive"))
    )
    (net (code "72") (name "unconnected-(JP15-Pad3)") (class "Default")
      (node (ref "JP15") (pin "3") (pinfunction "3_3") (pintype "passive"))
    )
    (net (code "73") (name "unconnected-(JP15-Pad4)") (class "Default")
      (node (ref "JP15") (pin "4") (pinfunction "4_4") (pintype "passive"))
    )
    (net (code "74") (name "unconnected-(JP15-Pad5)") (class "Default")
      (node (ref "JP15") (pin "5") (pinfunction "5_5") (pintype "passive"))
    )
    (net (code "75") (name "unconnected-(JP15-Pad6)") (class "Default")
      (node (ref "JP15") (pin "6") (pinfunction "6_6") (pintype "passive"))
    )
    (net (code "76") (name "unconnected-(JP15-Pad7)") (class "Default")
      (node (ref "JP15") (pin "7") (pinfunction "7_7") (pintype "passive"))
    )
    (net (code "77") (name "unconnected-(JP15-Pad8)") (class "Default")
      (node (ref "JP15") (pin "8") (pinfunction "8_8") (pintype "passive"))
    )
    (net (code "78") (name "unconnected-(JP15-Pad9)") (class "Default")
      (node (ref "JP15") (pin "9") (pinfunction "9_9") (pintype "passive"))
    )
    (net (code "79") (name "unconnected-(JP15-Pad10)") (class "Default")
      (node (ref "JP15") (pin "10") (pinfunction "10_10") (pintype "passive"))
    )
    (net (code "80") (name "unconnected-(JP15-Pad11)") (class "Default")
      (node (ref "JP15") (pin "11") (pinfunction "11_11") (pintype "passive"))
    )
    (net (code "81") (name "unconnected-(JP16-Pad1)") (class "Default")
      (node (ref "JP16") (pin "1") (pinfunction "1_1") (pintype "passive"))
    )
    (net (code "82") (name "unconnected-(JP16-Pad2)") (class "Default")
      (node (ref "JP16") (pin "2") (pinfunction "2_2") (pintype "passive"))
    )
    (net (code "83") (name "unconnected-(JP16-Pad3)") (class "Default")
      (node (ref "JP16") (pin "3") (pinfunction "3_3") (pintype "passive"))
    )
    (net (code "84") (name "unconnected-(JP16-Pad4)") (class "Default")
      (node (ref "JP16") (pin "4") (pinfunction "4_4") (pintype "passive"))
    )
    (net (code "85") (name "unconnected-(JP16-Pad5)") (class "Default")
      (node (ref "JP16") (pin "5") (pinfunction "5_5") (pintype "passive"))
    )
    (net (code "86") (name "unconnected-(JP16-Pad6)") (class "Default")
      (node (ref "JP16") (pin "6") (pinfunction "6_6") (pintype "passive"))
    )
    (net (code "87") (name "unconnected-(JP16-Pad7)") (class "Default")
      (node (ref "JP16") (pin "7") (pinfunction "7_7") (pintype "passive"))
    )
    (net (code "88") (name "unconnected-(JP16-Pad8)") (class "Default")
      (node (ref "JP16") (pin "8") (pinfunction "8_8") (pintype "passive"))
    )
    (net (code "89") (name "unconnected-(JP16-Pad9)") (class "Default")
      (node (ref "JP16") (pin "9") (pinfunction "9_9") (pintype "passive"))
    )
    (net (code "90") (name "unconnected-(JP16-Pad10)") (class "Default")
      (node (ref "JP16") (pin "10") (pinfunction "10_10") (pintype "passive"))
    )
    (net (code "91") (name "unconnected-(JP16-Pad11)") (class "Default")
      (node (ref "JP16") (pin "11") (pinfunction "11_11") (pintype "passive"))
    )
    (net (code "92") (name "unconnected-(JP17-Pad1)") (class "Default")
      (node (ref "JP17") (pin "1") (pinfunction "1_1") (pintype "passive"))
    )
    (net (code "93") (name "unconnected-(JP17-Pad2)") (class "Default")
      (node (ref "JP17") (pin "2") (pinfunction "2_2") (pintype "passive"))
    )
    (net (code "94") (name "unconnected-(JP17-Pad3)") (class "Default")
      (node (ref "JP17") (pin "3") (pinfunction "3_3") (pintype "passive"))
    )
    (net (code "95") (name "unconnected-(JP17-Pad4)") (class "Default")
      (node (ref "JP17") (pin "4") (pinfunction "4_4") (pintype "passive"))
    )
    (net (code "96") (name "unconnected-(JP17-Pad5)") (class "Default")
      (node (ref "JP17") (pin "5") (pinfunction "5_5") (pintype "passive"))
    )
    (net (code "97") (name "unconnected-(JP17-Pad6)") (class "Default")
      (node (ref "JP17") (pin "6") (pinfunction "6_6") (pintype "passive"))
    )
    (net (code "98") (name "unconnected-(JP17-Pad7)") (class "Default")
      (node (ref "JP17") (pin "7") (pinfunction "7_7") (pintype "passive"))
    )
    (net (code "99") (name "unconnected-(JP17-Pad8)") (class "Default")
      (node (ref "JP17") (pin "8") (pinfunction "8_8") (pintype "passive"))
    )
    (net (code "100") (name "unconnected-(JP17-Pad9)") (class "Default")
      (node (ref "JP17") (pin "9") (pinfunction "9_9") (pintype "passive"))
    )
    (net (code "101") (name "unconnected-(JP18-Pad1)") (class "Default")
      (node (ref "JP18") (pin "1") (pinfunction "1_1") (pintype "passive"))
    )
    (net (code "102") (name "unconnected-(JP18-Pad2)") (class "Default")
      (node (ref "JP18") (pin "2") (pinfunction "2_2") (pintype "passive"))
    )
    (net (code "103") (name "unconnected-(JP18-Pad3)") (class "Default")
      (node (ref "JP18") (pin "3") (pinfunction "3_3") (pintype "passive"))
    )
    (net (code "104") (name "unconnected-(JP18-Pad4)") (class "Default")
      (node (ref "JP18") (pin "4") (pinfunction "4_4") (pintype "passive"))
    )
    (net (code "105") (name "unconnected-(JP18-Pad5)") (class "Default")
      (node (ref "JP18") (pin "5") (pinfunction "5_5") (pintype "passive"))
    )
    (net (code "106") (name "unconnected-(JP18-Pad6)") (class "Default")
      (node (ref "JP18") (pin "6") (pinfunction "6_6") (pintype "passive"))
    )
    (net (code "107") (name "unconnected-(JP18-Pad7)") (class "Default")
      (node (ref "JP18") (pin "7") (pinfunction "7_7") (pintype "passive"))
    )
    (net (code "108") (name "unconnected-(JP18-Pad8)") (class "Default")
      (node (ref "JP18") (pin "8") (pinfunction "8_8") (pintype "passive"))
    )
    (net (code "109") (name "unconnected-(JP18-Pad9)") (class "Default")
      (node (ref "JP18") (pin "9") (pinfunction "9_9") (pintype "passive"))
    )
    (net (code "110") (name "unconnected-(JP21-Pad1)") (class "Default")
      (node (ref "JP21") (pin "1") (pinfunction "1_1") (pintype "passive"))
    )
    (net (code "111") (name "unconnected-(JP21-Pad2)") (class "Default")
      (node (ref "JP21") (pin "2") (pinfunction "2_2") (pintype "passive"))
    )
    (net (code "112") (name "unconnected-(JP21-Pad3)") (class "Default")
      (node (ref "JP21") (pin "3") (pinfunction "3_3") (pintype "passive"))
    )
    (net (code "113") (name "unconnected-(JP21-Pad4)") (class "Default")
      (node (ref "JP21") (pin "4") (pinfunction "4_4") (pintype "passive"))
    )
    (net (code "114") (name "unconnected-(JP21-Pad5)") (class "Default")
      (node (ref "JP21") (pin "5") (pinfunction "5_5") (pintype "passive"))
    )
    (net (code "115") (name "unconnected-(JP21-Pad6)") (class "Default")
      (node (ref "JP21") (pin "6") (pinfunction "6_6") (pintype "passive"))
    )
    (net (code "116") (name "unconnected-(JP21-Pad7)") (class "Default")
      (node (ref "JP21") (pin "7") (pinfunction "7_7") (pintype "passive"))
    )
    (net (code "117") (name "unconnected-(JP21-Pad8)") (class "Default")
      (node (ref "JP21") (pin "8") (pinfunction "8_8") (pintype "passive"))
    )
    (net (code "118") (name "unconnected-(JP21-Pad9)") (class "Default")
      (node (ref "JP21") (pin "9") (pinfunction "9_9") (pintype "passive"))
    )
    (net (code "119") (name "unconnected-(JP21-Pad10)") (class "Default")
      (node (ref "JP21") (pin "10") (pinfunction "10_10") (pintype "passive"))
    )
    (net (code "120") (name "unconnected-(JP23-Pad1)") (class "Default")
      (node (ref "JP23") (pin "1") (pinfunction "1_1") (pintype "passive"))
    )
    (net (code "121") (name "unconnected-(JP23-Pad2)") (class "Default")
      (node (ref "JP23") (pin "2") (pinfunction "2_2") (pintype "passive"))
    )
    (net (code "122") (name "unconnected-(JP23-Pad3)") (class "Default")
      (node (ref "JP23") (pin "3") (pinfunction "3_3") (pintype "passive"))
    )
    (net (code "123") (name "unconnected-(JP23-Pad4)") (class "Default")
      (node (ref "JP23") (pin "4") (pinfunction "4_4") (pintype "passive"))
    )
    (net (code "124") (name "unconnected-(JP23-Pad5)") (class "Default")
      (node (ref "JP23") (pin "5") (pinfunction "5_5") (pintype "passive"))
    )
    (net (code "125") (name "unconnected-(JP23-Pad6)") (class "Default")
      (node (ref "JP23") (pin "6") (pinfunction "6_6") (pintype "passive"))
    )
    (net (code "126") (name "unconnected-(JP23-Pad7)") (class "Default")
      (node (ref "JP23") (pin "7") (pinfunction "7_7") (pintype "passive"))
    )
    (net (code "127") (name "unconnected-(JP23-Pad8)") (class "Default")
      (node (ref "JP23") (pin "8") (pinfunction "8_8") (pintype "passive"))
    )
    (net (code "128") (name "unconnected-(JP23-Pad9)") (class "Default")
      (node (ref "JP23") (pin "9") (pinfunction "9_9") (pintype "passive"))
    )
    (net (code "129") (name "unconnected-(JP23-Pad10)") (class "Default")
      (node (ref "JP23") (pin "10") (pinfunction "10_10") (pintype "passive"))
    )
    (net (code "130") (name "unconnected-(JP23-Pad11)") (class "Default")
      (node (ref "JP23") (pin "11") (pinfunction "11_11") (pintype "passive"))
    )
    (net (code "131") (name "unconnected-(JP25-Pad1)") (class "Default")
      (node (ref "JP25") (pin "1") (pinfunction "1_1") (pintype "passive"))
    )
    (net (code "132") (name "unconnected-(JP25-Pad2)") (class "Default")
      (node (ref "JP25") (pin "2") (pinfunction "2_2") (pintype "passive"))
    )
    (net (code "133") (name "unconnected-(JP25-Pad3)") (class "Default")
      (node (ref "JP25") (pin "3") (pinfunction "3_3") (pintype "passive"))
    )
    (net (code "134") (name "unconnected-(JP25-Pad4)") (class "Default")
      (node (ref "JP25") (pin "4") (pinfunction "4_4") (pintype "passive"))
    )
    (net (code "135") (name "unconnected-(JP25-Pad5)") (class "Default")
      (node (ref "JP25") (pin "5") (pinfunction "5_5") (pintype "passive"))
    )
    (net (code "136") (name "unconnected-(JP25-Pad6)") (class "Default")
      (node (ref "JP25") (pin "6") (pinfunction "6_6") (pintype "passive"))
    )
    (net (code "137") (name "unconnected-(JP25-Pad7)") (class "Default")
      (node (ref "JP25") (pin "7") (pinfunction "7_7") (pintype "passive"))
    )
    (net (code "138") (name "unconnected-(JP25-Pad8)") (class "Default")
      (node (ref "JP25") (pin "8") (pinfunction "8_8") (pintype "passive"))
    )
    (net (code "139") (name "unconnected-(JP25-Pad9)") (class "Default")
      (node (ref "JP25") (pin "9") (pinfunction "9_9") (pintype "passive"))
    )
    (net (code "140") (name "unconnected-(JP25-Pad10)") (class "Default")
      (node (ref "JP25") (pin "10") (pinfunction "10_10") (pintype "passive"))
    )
    (net (code "141") (name "unconnected-(JP25-Pad11)") (class "Default")
      (node (ref "JP25") (pin "11") (pinfunction "11_11") (pintype "passive"))
    )
    (net (code "142") (name "unconnected-(JP26-Pad1)") (class "Default")
      (node (ref "JP26") (pin "1") (pinfunction "1_1") (pintype "passive"))
    )
    (net (code "143") (name "unconnected-(JP26-Pad2)") (class "Default")
      (node (ref "JP26") (pin "2") (pinfunction "2_2") (pintype "passive"))
    )
    (net (code "144") (name "unconnected-(JP26-Pad3)") (class "Default")
      (node (ref "JP26") (pin "3") (pinfunction "3_3") (pintype "passive"))
    )
    (net (code "145") (name "unconnected-(JP26-Pad4)") (class "Default")
      (node (ref "JP26") (pin "4") (pinfunction "4_4") (pintype "passive"))
    )
    (net (code "146") (name "unconnected-(JP26-Pad5)") (class "Default")
      (node (ref "JP26") (pin "5") (pinfunction "5_5") (pintype "passive"))
    )
    (net (code "147") (name "unconnected-(JP26-Pad6)") (class "Default")
      (node (ref "JP26") (pin "6") (pinfunction "6_6") (pintype "passive"))
    )
    (net (code "148") (name "unconnected-(JP26-Pad7)") (class "Default")
      (node (ref "JP26") (pin "7") (pinfunction "7_7") (pintype "passive"))
    )
    (net (code "149") (name "unconnected-(JP26-Pad8)") (class "Default")
      (node (ref "JP26") (pin "8") (pinfunction "8_8") (pintype "passive"))
    )
    (net (code "150") (name "unconnected-(JP26-Pad9)") (class "Default")
      (node (ref "JP26") (pin "9") (pinfunction "9_9") (pintype "passive"))
    )
    (net (code "151") (name "unconnected-(JP26-Pad10)") (class "Default")
      (node (ref "JP26") (pin "10") (pinfunction "10_10") (pintype "passive"))
    )
    (net (code "152") (name "unconnected-(JP26-Pad11)") (class "Default")
      (node (ref "JP26") (pin "11") (pinfunction "11_11") (pintype "passive"))
    )
    (net (code "153") (name "unconnected-(JP27-Pad1)") (class "Default")
      (node (ref "JP27") (pin "1") (pinfunction "1_1") (pintype "passive"))
    )
    (net (code "154") (name "unconnected-(JP27-Pad2)") (class "Default")
      (node (ref "JP27") (pin "2") (pinfunction "2_2") (pintype "passive"))
    )
    (net (code "155") (name "unconnected-(JP27-Pad3)") (class "Default")
      (node (ref "JP27") (pin "3") (pinfunction "3_3") (pintype "passive"))
    )
    (net (code "156") (name "unconnected-(JP27-Pad4)") (class "Default")
      (node (ref "JP27") (pin "4") (pinfunction "4_4") (pintype "passive"))
    )
    (net (code "157") (name "unconnected-(JP27-Pad5)") (class "Default")
      (node (ref "JP27") (pin "5") (pinfunction "5_5") (pintype "passive"))
    )
    (net (code "158") (name "unconnected-(JP27-Pad6)") (class "Default")
      (node (ref "JP27") (pin "6") (pinfunction "6_6") (pintype "passive"))
    )
    (net (code "159") (name "unconnected-(JP27-Pad7)") (class "Default")
      (node (ref "JP27") (pin "7") (pinfunction "7_7") (pintype "passive"))
    )
    (net (code "160") (name "unconnected-(JP27-Pad8)") (class "Default")
      (node (ref "JP27") (pin "8") (pinfunction "8_8") (pintype "passive"))
    )
    (net (code "161") (name "unconnected-(JP27-Pad9)") (class "Default")
      (node (ref "JP27") (pin "9") (pinfunction "9_9") (pintype "passive"))
    )
    (net (code "162") (name "unconnected-(JP27-Pad10)") (class "Default")
      (node (ref "JP27") (pin "10") (pinfunction "10_10") (pintype "passive"))
    )
    (net (code "163") (name "unconnected-(JP27-Pad11)") (class "Default")
      (node (ref "JP27") (pin "11") (pinfunction "11_11") (pintype "passive"))
    )
    (net (code "164") (name "unconnected-(JP28-Pad1)") (class "Default")
      (node (ref "JP28") (pin "1") (pinfunction "1_1") (pintype "passive"))
    )
    (net (code "165") (name "unconnected-(JP28-Pad2)") (class "Default")
      (node (ref "JP28") (pin "2") (pinfunction "2_2") (pintype "passive"))
    )
    (net (code "166") (name "unconnected-(JP28-Pad3)") (class "Default")
      (node (ref "JP28") (pin "3") (pinfunction "3_3") (pintype "passive"))
    )
    (net (code "167") (name "unconnected-(JP28-Pad4)") (class "Default")
      (node (ref "JP28") (pin "4") (pinfunction "4_4") (pintype "passive"))
    )
    (net (code "168") (name "unconnected-(JP28-Pad5)") (class "Default")
      (node (ref "JP28") (pin "5") (pinfunction "5_5") (pintype "passive"))
    )
    (net (code "169") (name "unconnected-(JP28-Pad6)") (class "Default")
      (node (ref "JP28") (pin "6") (pinfunction "6_6") (pintype "passive"))
    )
    (net (code "170") (name "unconnected-(JP28-Pad7)") (class "Default")
      (node (ref "JP28") (pin "7") (pinfunction "7_7") (pintype "passive"))
    )
    (net (code "171") (name "unconnected-(JP28-Pad8)") (class "Default")
      (node (ref "JP28") (pin "8") (pinfunction "8_8") (pintype "passive"))
    )
    (net (code "172") (name "unconnected-(JP28-Pad9)") (class "Default")
      (node (ref "JP28") (pin "9") (pinfunction "9_9") (pintype "passive"))
    )
    (net (code "173") (name "unconnected-(JP28-Pad10)") (class "Default")
      (node (ref "JP28") (pin "10") (pinfunction "10_10") (pintype "passive"))
    )
    (net (code "174") (name "unconnected-(JP28-Pad11)") (class "Default")
      (node (ref "JP28") (pin "11") (pinfunction "11_11") (pintype "passive"))
    )
    (net (code "175") (name "unconnected-(JP29-Pad1)") (class "Default")
      (node (ref "JP29") (pin "1") (pinfunction "1_1") (pintype "passive"))
    )
    (net (code "176") (name "unconnected-(JP29-Pad2)") (class "Default")
      (node (ref "JP29") (pin "2") (pinfunction "2_2") (pintype "passive"))
    )
    (net (code "177") (name "unconnected-(JP29-Pad3)") (class "Default")
      (node (ref "JP29") (pin "3") (pinfunction "3_3") (pintype "passive"))
    )
    (net (code "178") (name "unconnected-(JP29-Pad4)") (class "Default")
      (node (ref "JP29") (pin "4") (pinfunction "4_4") (pintype "passive"))
    )
    (net (code "179") (name "unconnected-(JP29-Pad5)") (class "Default")
      (node (ref "JP29") (pin "5") (pinfunction "5_5") (pintype "passive"))
    )
    (net (code "180") (name "unconnected-(JP29-Pad6)") (class "Default")
      (node (ref "JP29") (pin "6") (pinfunction "6_6") (pintype "passive"))
    )
    (net (code "181") (name "unconnected-(JP29-Pad7)") (class "Default")
      (node (ref "JP29") (pin "7") (pinfunction "7_7") (pintype "passive"))
    )
    (net (code "182") (name "unconnected-(JP29-Pad8)") (class "Default")
      (node (ref "JP29") (pin "8") (pinfunction "8_8") (pintype "passive"))
    )
    (net (code "183") (name "unconnected-(JP29-Pad9)") (class "Default")
      (node (ref "JP29") (pin "9") (pinfunction "9_9") (pintype "passive"))
    )
    (net (code "184") (name "unconnected-(JP29-Pad10)") (class "Default")
      (node (ref "JP29") (pin "10") (pinfunction "10_10") (pintype "passive"))
    )
    (net (code "185") (name "unconnected-(JP29-Pad11)") (class "Default")
      (node (ref "JP29") (pin "11") (pinfunction "11_11") (pintype "passive"))
    )
    (net (code "186") (name "unconnected-(JP30-Pad1)") (class "Default")
      (node (ref "JP30") (pin "1") (pinfunction "1_1") (pintype "passive"))
    )
    (net (code "187") (name "unconnected-(JP30-Pad2)") (class "Default")
      (node (ref "JP30") (pin "2") (pinfunction "2_2") (pintype "passive"))
    )
    (net (code "188") (name "unconnected-(JP30-Pad3)") (class "Default")
      (node (ref "JP30") (pin "3") (pinfunction "3_3") (pintype "passive"))
    )
    (net (code "189") (name "unconnected-(JP30-Pad4)") (class "Default")
      (node (ref "JP30") (pin "4") (pinfunction "4_4") (pintype "passive"))
    )
    (net (code "190") (name "unconnected-(JP30-Pad5)") (class "Default")
      (node (ref "JP30") (pin "5") (pinfunction "5_5") (pintype "passive"))
    )
    (net (code "191") (name "unconnected-(JP30-Pad6)") (class "Default")
      (node (ref "JP30") (pin "6") (pinfunction "6_6") (pintype "passive"))
    )
    (net (code "192") (name "unconnected-(JP30-Pad7)") (class "Default")
      (node (ref "JP30") (pin "7") (pinfunction "7_7") (pintype "passive"))
    )
    (net (code "193") (name "unconnected-(JP30-Pad8)") (class "Default")
      (node (ref "JP30") (pin "8") (pinfunction "8_8") (pintype "passive"))
    )
    (net (code "194") (name "unconnected-(JP30-Pad9)") (class "Default")
      (node (ref "JP30") (pin "9") (pinfunction "9_9") (pintype "passive"))
    )
    (net (code "195") (name "unconnected-(JP30-Pad10)") (class "Default")
      (node (ref "JP30") (pin "10") (pinfunction "10_10") (pintype "passive"))
    )
    (net (code "196") (name "unconnected-(JP31-Pad1)") (class "Default")
      (node (ref "JP31") (pin "1") (pinfunction "1_1") (pintype "passive"))
    )
    (net (code "197") (name "unconnected-(JP31-Pad2)") (class "Default")
      (node (ref "JP31") (pin "2") (pinfunction "2_2") (pintype "passive"))
    )
    (net (code "198") (name "unconnected-(JP31-Pad3)") (class "Default")
      (node (ref "JP31") (pin "3") (pinfunction "3_3") (pintype "passive"))
    )
    (net (code "199") (name "unconnected-(JP31-Pad4)") (class "Default")
      (node (ref "JP31") (pin "4") (pinfunction "4_4") (pintype "passive"))
    )
    (net (code "200") (name "unconnected-(JP31-Pad5)") (class "Default")
      (node (ref "JP31") (pin "5") (pinfunction "5_5") (pintype "passive"))
    )
    (net (code "201") (name "unconnected-(JP31-Pad6)") (class "Default")
      (node (ref "JP31") (pin "6") (pinfunction "6_6") (pintype "passive"))
    )
    (net (code "202") (name "unconnected-(JP31-Pad7)") (class "Default")
      (node (ref "JP31") (pin "7") (pinfunction "7_7") (pintype "passive"))
    )
    (net (code "203") (name "unconnected-(JP31-Pad8)") (class "Default")
      (node (ref "JP31") (pin "8") (pinfunction "8_8") (pintype "passive"))
    )
    (net (code "204") (name "unconnected-(JP31-Pad9)") (class "Default")
      (node (ref "JP31") (pin "9") (pinfunction "9_9") (pintype "passive"))
    )
    (net (code "205") (name "unconnected-(JP32-Pad1)") (class "Default")
      (node (ref "JP32") (pin "1") (pinfunction "1_1") (pintype "passive"))
    )
    (net (code "206") (name "unconnected-(JP32-Pad2)") (class "Default")
      (node (ref "JP32") (pin "2") (pinfunction "2_2") (pintype "passive"))
    )
    (net (code "207") (name "unconnected-(JP32-Pad3)") (class "Default")
      (node (ref "JP32") (pin "3") (pinfunction "3_3") (pintype "passive"))
    )
    (net (code "208") (name "unconnected-(JP32-Pad4)") (class "Default")
      (node (ref "JP32") (pin "4") (pinfunction "4_4") (pintype "passive"))
    )
    (net (code "209") (name "unconnected-(JP32-Pad5)") (class "Default")
      (node (ref "JP32") (pin "5") (pinfunction "5_5") (pintype "passive"))
    )
    (net (code "210") (name "unconnected-(JP32-Pad6)") (class "Default")
      (node (ref "JP32") (pin "6") (pinfunction "6_6") (pintype "passive"))
    )
    (net (code "211") (name "unconnected-(JP32-Pad7)") (class "Default")
      (node (ref "JP32") (pin "7") (pinfunction "7_7") (pintype "passive"))
    )
    (net (code "212") (name "unconnected-(JP32-Pad8)") (class "Default")
      (node (ref "JP32") (pin "8") (pinfunction "8_8") (pintype "passive"))
    )
    (net (code "213") (name "unconnected-(JP32-Pad9)") (class "Default")
      (node (ref "JP32") (pin "9") (pinfunction "9_9") (pintype "passive"))
    )
    (net (code "214") (name "unconnected-(JP32-Pad10)") (class "Default")
      (node (ref "JP32") (pin "10") (pinfunction "10_10") (pintype "passive"))
    )
    (net (code "215") (name "unconnected-(JP32-Pad11)") (class "Default")
      (node (ref "JP32") (pin "11") (pinfunction "11_11") (pintype "passive"))
    )
    (net (code "216") (name "unconnected-(JP33-Pad1)") (class "Default")
      (node (ref "JP33") (pin "1") (pinfunction "1_1") (pintype "passive"))
    )
    (net (code "217") (name "unconnected-(JP33-Pad2)") (class "Default")
      (node (ref "JP33") (pin "2") (pinfunction "2_2") (pintype "passive"))
    )
    (net (code "218") (name "unconnected-(JP33-Pad3)") (class "Default")
      (node (ref "JP33") (pin "3") (pinfunction "3_3") (pintype "passive"))
    )
    (net (code "219") (name "unconnected-(JP33-Pad4)") (class "Default")
      (node (ref "JP33") (pin "4") (pinfunction "4_4") (pintype "passive"))
    )
    (net (code "220") (name "unconnected-(JP33-Pad5)") (class "Default")
      (node (ref "JP33") (pin "5") (pinfunction "5_5") (pintype "passive"))
    )
    (net (code "221") (name "unconnected-(JP33-Pad6)") (class "Default")
      (node (ref "JP33") (pin "6") (pinfunction "6_6") (pintype "passive"))
    )
    (net (code "222") (name "unconnected-(JP33-Pad7)") (class "Default")
      (node (ref "JP33") (pin "7") (pinfunction "7_7") (pintype "passive"))
    )
    (net (code "223") (name "unconnected-(JP33-Pad8)") (class "Default")
      (node (ref "JP33") (pin "8") (pinfunction "8_8") (pintype "passive"))
    )
    (net (code "224") (name "unconnected-(JP33-Pad9)") (class "Default")
      (node (ref "JP33") (pin "9") (pinfunction "9_9") (pintype "passive"))
    )
    (net (code "225") (name "unconnected-(JP34-Pad1)") (class "Default")
      (node (ref "JP34") (pin "1") (pinfunction "1_1") (pintype "passive"))
    )
    (net (code "226") (name "unconnected-(JP34-Pad2)") (class "Default")
      (node (ref "JP34") (pin "2") (pinfunction "2_2") (pintype "passive"))
    )
    (net (code "227") (name "unconnected-(JP34-Pad3)") (class "Default")
      (node (ref "JP34") (pin "3") (pinfunction "3_3") (pintype "passive"))
    )
    (net (code "228") (name "unconnected-(JP34-Pad4)") (class "Default")
      (node (ref "JP34") (pin "4") (pinfunction "4_4") (pintype "passive"))
    )
    (net (code "229") (name "unconnected-(JP34-Pad5)") (class "Default")
      (node (ref "JP34") (pin "5") (pinfunction "5_5") (pintype "passive"))
    )
    (net (code "230") (name "unconnected-(JP34-Pad6)") (class "Default")
      (node (ref "JP34") (pin "6") (pinfunction "6_6") (pintype "passive"))
    )
    (net (code "231") (name "unconnected-(JP34-Pad7)") (class "Default")
      (node (ref "JP34") (pin "7") (pinfunction "7_7") (pintype "passive"))
    )
    (net (code "232") (name "unconnected-(JP34-Pad8)") (class "Default")
      (node (ref "JP34") (pin "8") (pinfunction "8_8") (pintype "passive"))
    )
    (net (code "233") (name "unconnected-(JP34-Pad9)") (class "Default")
      (node (ref "JP34") (pin "9") (pinfunction "9_9") (pintype "passive"))
    )
    (net (code "234") (name "unconnected-(JP34-Pad10)") (class "Default")
      (node (ref "JP34") (pin "10") (pinfunction "10_10") (pintype "passive"))
    )
    (net (code "235") (name "unconnected-(JP34-Pad11)") (class "Default")
      (node (ref "JP34") (pin "11") (pinfunction "11_11") (pintype "passive"))
    )
    (net (code "236") (name "unconnected-(JP35-Pad1)") (class "Default")
      (node (ref "JP35") (pin "1") (pinfunction "1_1") (pintype "passive"))
    )
    (net (code "237") (name "unconnected-(JP35-Pad2)") (class "Default")
      (node (ref "JP35") (pin "2") (pinfunction "2_2") (pintype "passive"))
    )
    (net (code "238") (name "unconnected-(JP35-Pad3)") (class "Default")
      (node (ref "JP35") (pin "3") (pinfunction "3_3") (pintype "passive"))
    )
    (net (code "239") (name "unconnected-(JP35-Pad4)") (class "Default")
      (node (ref "JP35") (pin "4") (pinfunction "4_4") (pintype "passive"))
    )
    (net (code "240") (name "unconnected-(JP35-Pad5)") (class "Default")
      (node (ref "JP35") (pin "5") (pinfunction "5_5") (pintype "passive"))
    )
    (net (code "241") (name "unconnected-(JP35-Pad6)") (class "Default")
      (node (ref "JP35") (pin "6") (pinfunction "6_6") (pintype "passive"))
    )
    (net (code "242") (name "unconnected-(JP35-Pad7)") (class "Default")
      (node (ref "JP35") (pin "7") (pinfunction "7_7") (pintype "passive"))
    )
    (net (code "243") (name "unconnected-(JP35-Pad8)") (class "Default")
      (node (ref "JP35") (pin "8") (pinfunction "8_8") (pintype "passive"))
    )
    (net (code "244") (name "unconnected-(JP35-Pad9)") (class "Default")
      (node (ref "JP35") (pin "9") (pinfunction "9_9") (pintype "passive"))
    )
    (net (code "245") (name "unconnected-(JP35-Pad10)") (class "Default")
      (node (ref "JP35") (pin "10") (pinfunction "10_10") (pintype "passive"))
    )
    (net (code "246") (name "unconnected-(JP36-Pad1)") (class "Default")
      (node (ref "JP36") (pin "1") (pinfunction "1_1") (pintype "passive"))
    )
    (net (code "247") (name "unconnected-(JP36-Pad2)") (class "Default")
      (node (ref "JP36") (pin "2") (pinfunction "2_2") (pintype "passive"))
    )
    (net (code "248") (name "unconnected-(JP36-Pad3)") (class "Default")
      (node (ref "JP36") (pin "3") (pinfunction "3_3") (pintype "passive"))
    )
    (net (code "249") (name "unconnected-(JP36-Pad4)") (class "Default")
      (node (ref "JP36") (pin "4") (pinfunction "4_4") (pintype "passive"))
    )
    (net (code "250") (name "unconnected-(JP36-Pad5)") (class "Default")
      (node (ref "JP36") (pin "5") (pinfunction "5_5") (pintype "passive"))
    )
    (net (code "251") (name "unconnected-(JP36-Pad6)") (class "Default")
      (node (ref "JP36") (pin "6") (pinfunction "6_6") (pintype "passive"))
    )
    (net (code "252") (name "unconnected-(JP36-Pad7)") (class "Default")
      (node (ref "JP36") (pin "7") (pinfunction "7_7") (pintype "passive"))
    )
    (net (code "253") (name "unconnected-(JP36-Pad8)") (class "Default")
      (node (ref "JP36") (pin "8") (pinfunction "8_8") (pintype "passive"))
    )
    (net (code "254") (name "unconnected-(JP37-Pad1)") (class "Default")
      (node (ref "JP37") (pin "1") (pinfunction "1_1") (pintype "passive"))
    )
    (net (code "255") (name "unconnected-(JP37-Pad2)") (class "Default")
      (node (ref "JP37") (pin "2") (pinfunction "2_2") (pintype "passive"))
    )
    (net (code "256") (name "unconnected-(JP37-Pad3)") (class "Default")
      (node (ref "JP37") (pin "3") (pinfunction "3_3") (pintype "passive"))
    )
    (net (code "257") (name "unconnected-(JP37-Pad4)") (class "Default")
      (node (ref "JP37") (pin "4") (pinfunction "4_4") (pintype "passive"))
    )
    (net (code "258") (name "unconnected-(JP37-Pad5)") (class "Default")
      (node (ref "JP37") (pin "5") (pinfunction "5_5") (pintype "passive"))
    )
    (net (code "259") (name "unconnected-(JP37-Pad6)") (class "Default")
      (node (ref "JP37") (pin "6") (pinfunction "6_6") (pintype "passive"))
    )
    (net (code "260") (name "unconnected-(JP37-Pad7)") (class "Default")
      (node (ref "JP37") (pin "7") (pinfunction "7_7") (pintype "passive"))
    )
    (net (code "261") (name "unconnected-(JP37-Pad8)") (class "Default")
      (node (ref "JP37") (pin "8") (pinfunction "8_8") (pintype "passive"))
    )
    (net (code "262") (name "unconnected-(JP38-Pad1)") (class "Default")
      (node (ref "JP38") (pin "1") (pinfunction "1_1") (pintype "passive"))
    )
    (net (code "263") (name "unconnected-(JP38-Pad2)") (class "Default")
      (node (ref "JP38") (pin "2") (pinfunction "2_2") (pintype "passive"))
    )
    (net (code "264") (name "unconnected-(JP38-Pad3)") (class "Default")
      (node (ref "JP38") (pin "3") (pinfunction "3_3") (pintype "passive"))
    )
    (net (code "265") (name "unconnected-(JP38-Pad4)") (class "Default")
      (node (ref "JP38") (pin "4") (pinfunction "4_4") (pintype "passive"))
    )
    (net (code "266") (name "unconnected-(JP38-Pad5)") (class "Default")
      (node (ref "JP38") (pin "5") (pinfunction "5_5") (pintype "passive"))
    )
    (net (code "267") (name "unconnected-(JP38-Pad6)") (class "Default")
      (node (ref "JP38") (pin "6") (pinfunction "6_6") (pintype "passive"))
    )
    (net (code "268") (name "unconnected-(JP38-Pad7)") (class "Default")
      (node (ref "JP38") (pin "7") (pinfunction "7_7") (pintype "passive"))
    )
    (net (code "269") (name "unconnected-(JP38-Pad8)") (class "Default")
      (node (ref "JP38") (pin "8") (pinfunction "8_8") (pintype "passive"))
    )
    (net (code "270") (name "unconnected-(JP39-Pad1)") (class "Default")
      (node (ref "JP39") (pin "1") (pinfunction "1_1") (pintype "passive"))
    )
    (net (code "271") (name "unconnected-(JP39-Pad2)") (class "Default")
      (node (ref "JP39") (pin "2") (pinfunction "2_2") (pintype "passive"))
    )
    (net (code "272") (name "unconnected-(JP39-Pad3)") (class "Default")
      (node (ref "JP39") (pin "3") (pinfunction "3_3") (pintype "passive"))
    )
    (net (code "273") (name "unconnected-(JP39-Pad4)") (class "Default")
      (node (ref "JP39") (pin "4") (pinfunction "4_4") (pintype "passive"))
    )
    (net (code "274") (name "unconnected-(JP39-Pad5)") (class "Default")
      (node (ref "JP39") (pin "5") (pinfunction "5_5") (pintype "passive"))
    )
    (net (code "275") (name "unconnected-(JP39-Pad6)") (class "Default")
      (node (ref "JP39") (pin "6") (pinfunction "6_6") (pintype "passive"))
    )
    (net (code "276") (name "unconnected-(JP39-Pad7)") (class "Default")
      (node (ref "JP39") (pin "7") (pinfunction "7_7") (pintype "passive"))
    )
    (net (code "277") (name "unconnected-(JP39-Pad8)") (class "Default")
      (node (ref "JP39") (pin "8") (pinfunction "8_8") (pintype "passive"))
    )
    (net (code "278") (name "unconnected-(JP43-Pad1)") (class "Default")
      (node (ref "JP43") (pin "1") (pinfunction "1_1") (pintype "passive"))
    )
    (net (code "279") (name "unconnected-(JP43-Pad2)") (class "Default")
      (node (ref "JP43") (pin "2") (pinfunction "2_2") (pintype "passive"))
    )
    (net (code "280") (name "unconnected-(JP44-Pad1)") (class "Default")
      (node (ref "JP44") (pin "1") (pinfunction "1_1") (pintype "passive"))
    )
    (net (code "281") (name "unconnected-(JP44-Pad2)") (class "Default")
      (node (ref "JP44") (pin "2") (pinfunction "2_2") (pintype "passive"))
    )
    (net (code "282") (name "unconnected-(JP60-Pad1)") (class "Default")
      (node (ref "JP60") (pin "1") (pinfunction "1_1") (pintype "passive"))
    )
    (net (code "283") (name "unconnected-(JP60-Pad2)") (class "Default")
      (node (ref "JP60") (pin "2") (pinfunction "2_2") (pintype "passive"))
    )
  )
)
